# WiLoV2.net
KiCad netlist of a schematic drawn in EAGLE
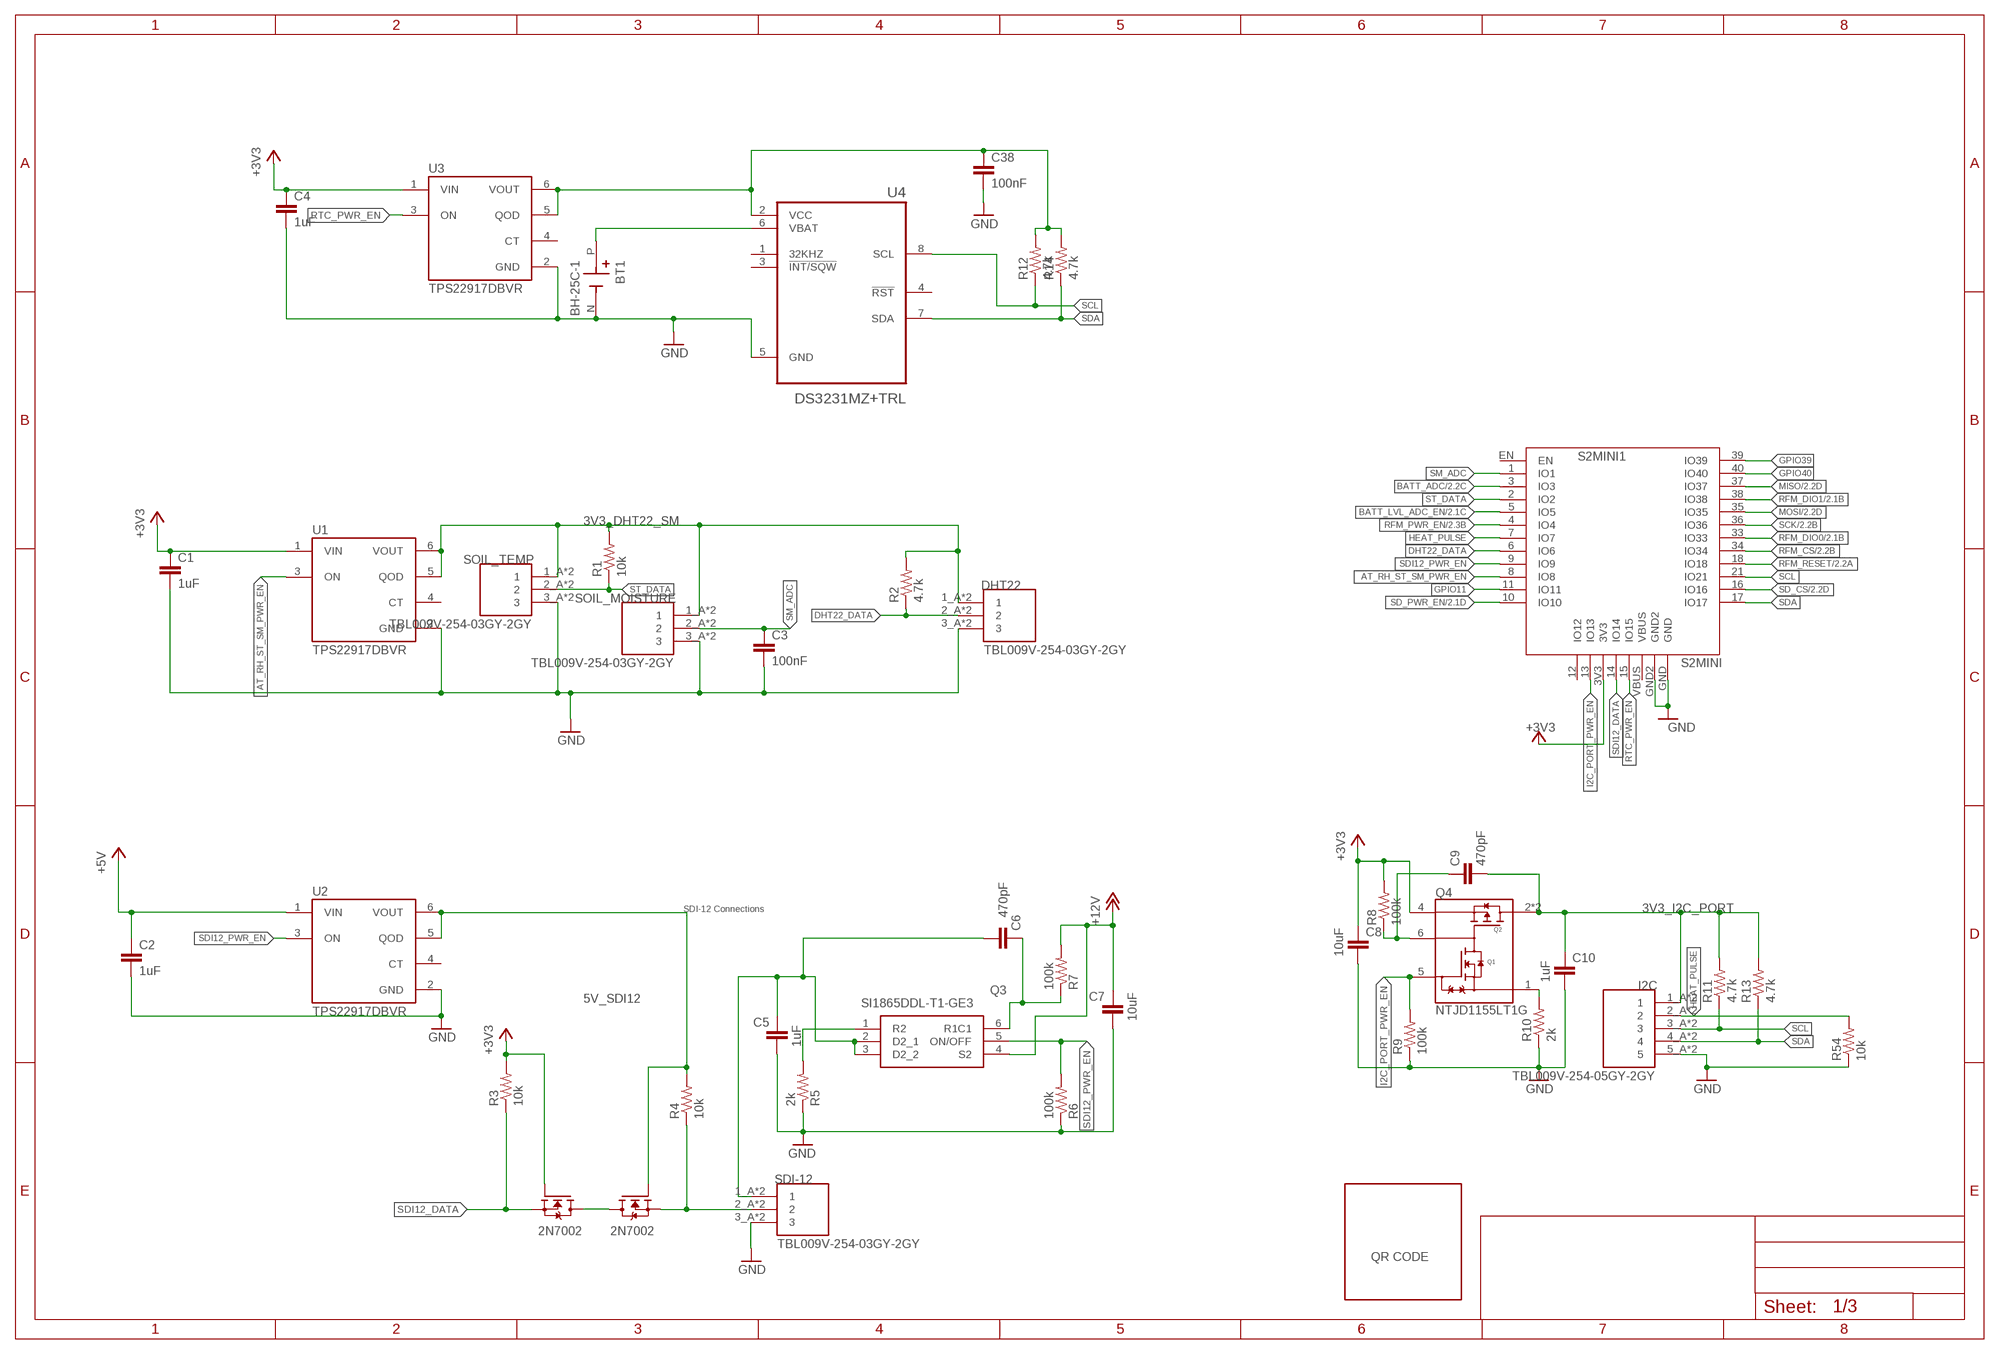
[diagram p0: schematic, sheet 1]
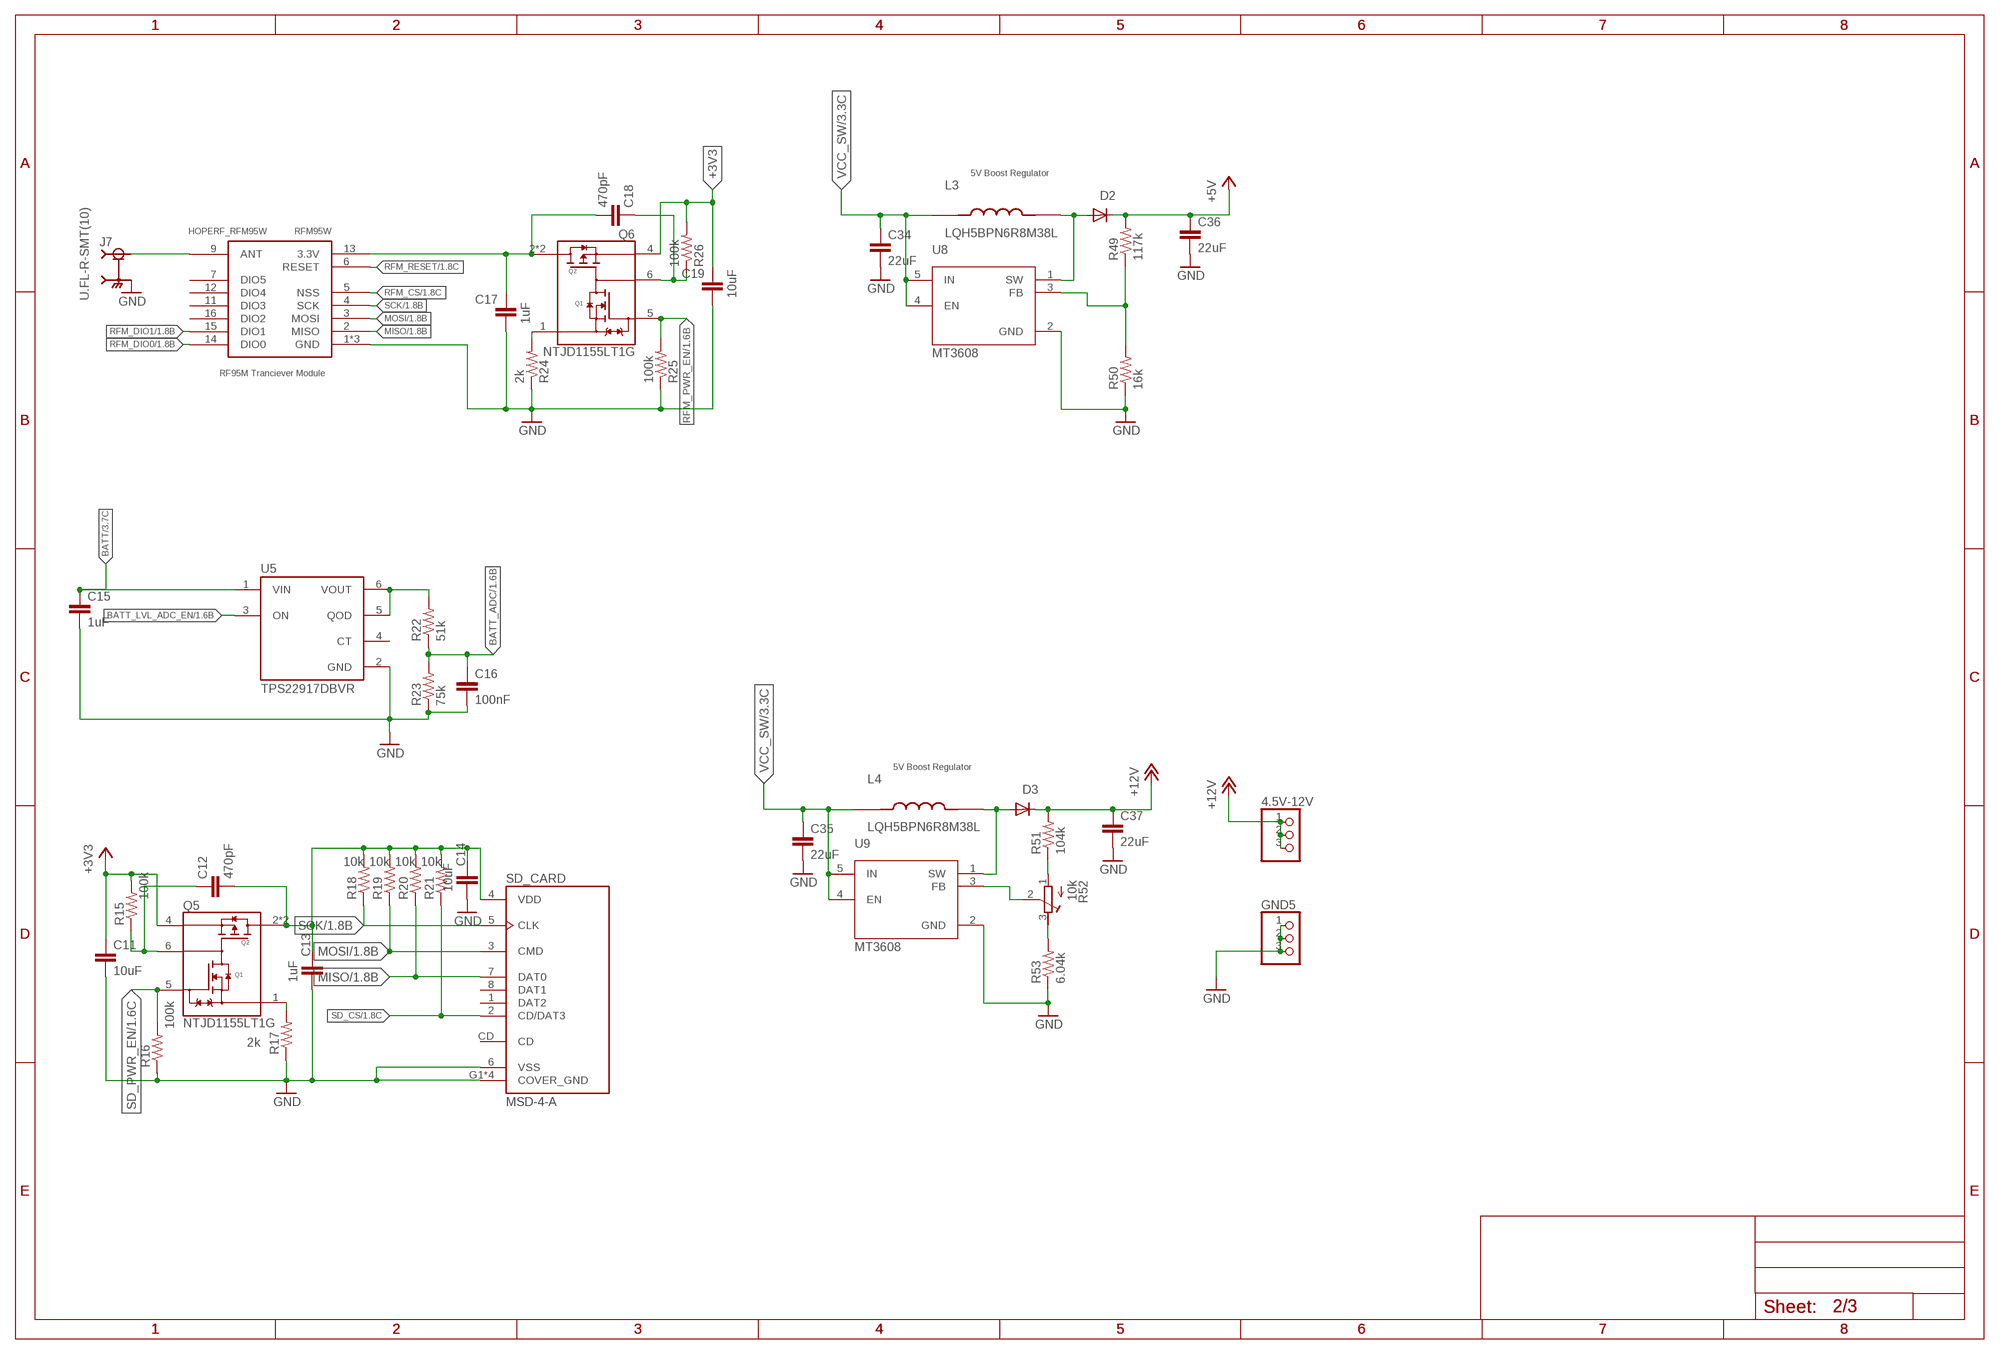
[diagram p1: schematic, sheet 2]
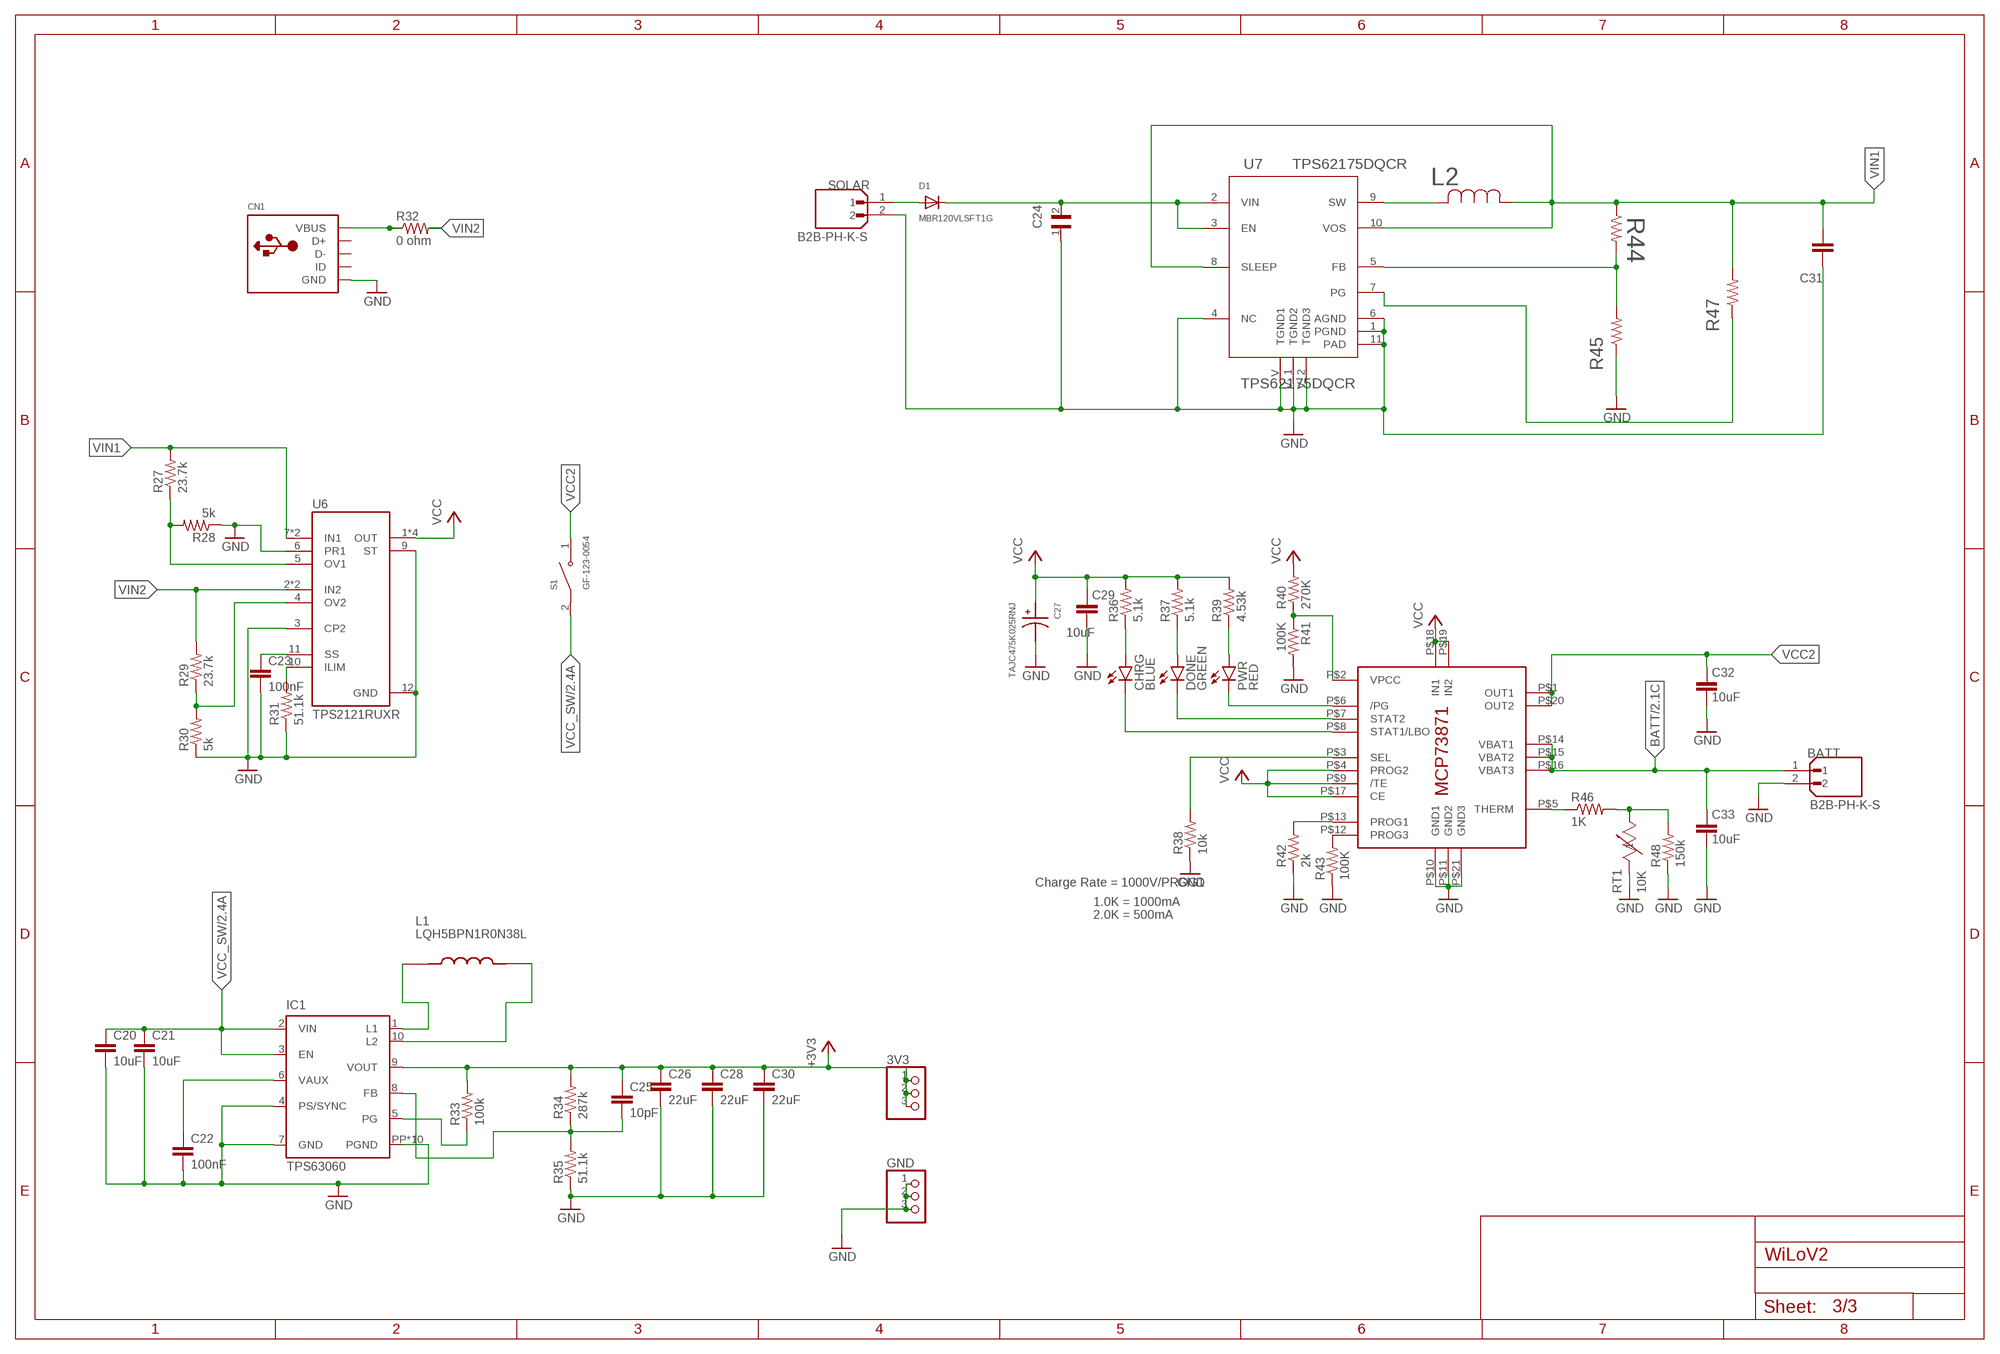
[diagram p2: schematic, sheet 3]

(export (version "E")
  (design (tool "Eeschema 10.0.6"))
  (components
    (comp (ref "3V3")
      (value "PINHD-1X3")
      (footprint "eagle-import:1X03")
      (fields (field (name "MPN") "61300311121"))
      (libsource (lib "eagle-import") (part "PINHD-1X3"))
    )
    (comp (ref "BATT")
      (value "B2B-PH-K-S")
      (footprint "eagle-import:JST_B2B-PH-K-S")
      (fields (field (name "MANUFACTURER") "JST"))
      (libsource (lib "eagle-import") (part "B2B-PH-K-S"))
    )
    (comp (ref "C20")
      (value "10uF")
      (footprint "eagle-import:C0805")
      (fields (field (name "MPN") "GRM21BR61C106KE15K"))
      (libsource (lib "eagle-import") (part "rcl@2_C-EUC0805"))
    )
    (comp (ref "C21")
      (value "10uF")
      (footprint "eagle-import:C0805")
      (fields (field (name "MPN") "GRM21BR61C106KE15K"))
      (libsource (lib "eagle-import") (part "rcl@2_C-EUC0805"))
    )
    (comp (ref "C22")
      (value "100nF")
      (footprint "eagle-import:C0805")
      (fields (field (name "MPN") "KGM21NR71E104KT"))
      (libsource (lib "eagle-import") (part "rcl@2_C-EUC0805"))
    )
    (comp (ref "C23")
      (value "100nF")
      (footprint "eagle-import:C0805")
      (fields (field (name "MPN") "KGM21NR71E104KT"))
      (libsource (lib "eagle-import") (part "rcl@2_C-EUC0805"))
    )
    (comp (ref "C24")
      (value "2.2uF")
      (footprint "eagle-import:CAPC2012X145N")
      (fields (field (name "MPN") "CGA4J3X7R1H225K125AB"))
      (libsource (lib "eagle-import") (part "CGA4J3X7R1H225K125AB"))
    )
    (comp (ref "C25")
      (value "10pF")
      (footprint "eagle-import:C0805")
      (fields (field (name "MPN") "C0805C100JDGACTU"))
      (libsource (lib "eagle-import") (part "rcl@2_C-EUC0805"))
    )
    (comp (ref "C26")
      (value "22uF")
      (footprint "eagle-import:C0805")
      (fields (field (name "MPN") "CL21A226MOQNNNE"))
      (libsource (lib "eagle-import") (part "rcl@2_C-EUC0805"))
    )
    (comp (ref "C27")
      (value "TAJC475K025RNJ")
      (footprint "eagle-import:CAPPM6032X280N")
      (fields (field (name "MANUFACTURER") "AVX"))
      (libsource (lib "eagle-import") (part "TAJC475K025RNJ"))
    )
    (comp (ref "C28")
      (value "22uF")
      (footprint "eagle-import:C0805")
      (fields (field (name "MPN") "CL21A226MOQNNNE"))
      (libsource (lib "eagle-import") (part "rcl@2_C-EUC0805"))
    )
    (comp (ref "C29")
      (value "10uF")
      (footprint "eagle-import:C0805")
      (fields (field (name "MPN") "GRM21BR61C106KE15K"))
      (libsource (lib "eagle-import") (part "rcl@2_C-EUC0805"))
    )
    (comp (ref "C30")
      (value "22uF")
      (footprint "eagle-import:C0805")
      (fields (field (name "MPN") "CL21A226MOQNNNE"))
      (libsource (lib "eagle-import") (part "rcl@2_C-EUC0805"))
    )
    (comp (ref "C31")
      (value "22uF")
      (footprint "eagle-import:C0805")
      (fields (field (name "MPN") "CL21A226MOQNNNE"))
      (libsource (lib "eagle-import") (part "rcl_334_C-EUC0805"))
    )
    (comp (ref "C32")
      (value "10uF")
      (footprint "eagle-import:C0805")
      (fields (field (name "MPN") "GRM21BR61C106KE15K"))
      (libsource (lib "eagle-import") (part "rcl@2_C-EUC0805"))
    )
    (comp (ref "C33")
      (value "10uF")
      (footprint "eagle-import:C0805")
      (fields (field (name "MPN") "GRM21BR61C106KE15K"))
      (libsource (lib "eagle-import") (part "rcl@2_C-EUC0805"))
    )
    (comp (ref "CHRG")
      (value "BLUE")
      (footprint "eagle-import:SML0603")
      (fields (field (name "MPN") "XZCFBB53W-8VF"))
      (libsource (lib "eagle-import") (part "LEDSML0603"))
    )
    (comp (ref "CN1")
      (value "USBMINIB")
      (footprint "eagle-import:USB-MINIB")
      (fields (field (name "MPN") "690-005-299-043"))
      (libsource (lib "eagle-import") (part "USBMINIB"))
    )
    (comp (ref "D1")
      (value "MBR120VLSFT1G")
      (footprint "eagle-import:SOD-123FL")
      (libsource (lib "eagle-import") (part "DIODE_SOD-123FL"))
    )
    (comp (ref "DONE")
      (value "GREEN")
      (footprint "eagle-import:SML0603")
      (fields (field (name "MPN") "XZCDGK53W-8VF"))
      (libsource (lib "eagle-import") (part "LEDSML0603"))
    )
    (comp (ref "GND")
      (value "PINHD-1X3")
      (footprint "eagle-import:1X03")
      (fields (field (name "MPN") "61300311121"))
      (libsource (lib "eagle-import") (part "PINHD-1X3"))
    )
    (comp (ref "IC1")
      (value "TPS63060")
      (footprint "eagle-import:DSC-S-PWSON-N10")
      (fields (field (name "MPN") "TPS63060DSCR"))
      (libsource (lib "eagle-import") (part "TPS63060"))
    )
    (comp (ref "IC2")
      (value "MCP73871")
      (footprint "eagle-import:QFN20_4MM")
      (fields (field (name "MPN") "MCP73871T-2CCI/ML"))
      (libsource (lib "eagle-import") (part "MCP73871"))
    )
    (comp (ref "L1")
      (value "LQH5BPN1R0N38L")
      (footprint "eagle-import:IND_LQH5BPN1R0N38L")
      (fields (field (name "MANUFACTURER") "Murata"))
      (libsource (lib "eagle-import") (part "LQH5BPN1R0N38L"))
    )
    (comp (ref "L2")
      (value "10uH")
      (footprint "eagle-import:IND_IFSC_1515AH_VIS-M")
      (fields
        (field (name "MANUFACTURER_PART_NUMBER") "IFSC1515AHER100M01")
        (field (name "COPYRIGHT") "Copyright (C) 2025 Ultra Librarian. All rights reserved.")
      )
      (libsource (lib "eagle-import") (part "IFSC1515AHER100M01IND_IFSC_1515AH_VIS-M"))
    )
    (comp (ref "PWR")
      (value "RED")
      (footprint "eagle-import:SML0603")
      (fields (field (name "MPN") "XZCM2CRK53WA-8VF"))
      (libsource (lib "eagle-import") (part "LEDSML0603"))
    )
    (comp (ref "R27")
      (value "23.7k")
      (footprint "eagle-import:R0603")
      (fields (field (name "MPN") "ERJ-3EKF2372V"))
      (libsource (lib "eagle-import") (part "rcl@2_R-US_R0603"))
    )
    (comp (ref "R28")
      (value "5k")
      (footprint "eagle-import:R0603")
      (fields (field (name "MPN") "RN73A1J5K0FTD"))
      (libsource (lib "eagle-import") (part "rcl@2_R-US_R0603"))
    )
    (comp (ref "R29")
      (value "23.7k")
      (footprint "eagle-import:R0603")
      (fields (field (name "MPN") "ERJ-3EKF2372V"))
      (libsource (lib "eagle-import") (part "rcl@2_R-US_R0603"))
    )
    (comp (ref "R30")
      (value "5k")
      (footprint "eagle-import:R0603")
      (fields (field (name "MPN") "RN73A1J5K0FTD"))
      (libsource (lib "eagle-import") (part "rcl@2_R-US_R0603"))
    )
    (comp (ref "R31")
      (value "51.1k")
      (footprint "eagle-import:R0603")
      (fields (field (name "MPN") "RC0603FR-0751K1L "))
      (libsource (lib "eagle-import") (part "R-US_R0603"))
    )
    (comp (ref "R32")
      (value "0 ohm")
      (footprint "eagle-import:R0805")
      (fields (field (name "MPN") "ERJ-6GEY0R00V"))
      (libsource (lib "eagle-import") (part "R-US_R0805"))
    )
    (comp (ref "R33")
      (value "100k")
      (footprint "eagle-import:R0603")
      (fields (field (name "MPN") "CRG0603F100K"))
      (libsource (lib "eagle-import") (part "rcl@2_R-US_R0603"))
    )
    (comp (ref "R34")
      (value "287k")
      (footprint "eagle-import:R0603")
      (fields (field (name "MPN") "ERJ-3EKF2873V"))
      (libsource (lib "eagle-import") (part "rcl_R-US_R0603"))
    )
    (comp (ref "R35")
      (value "51.1k")
      (footprint "eagle-import:R0603")
      (fields (field (name "MPN") "RC0603FR-0751K1L"))
      (libsource (lib "eagle-import") (part "rcl_R-US_R0603"))
    )
    (comp (ref "R36")
      (value "5.1k")
      (footprint "eagle-import:R0603")
      (fields (field (name "MPN") "ERA-3ARW512V"))
      (libsource (lib "eagle-import") (part "rcl@2_R-US_R0603"))
    )
    (comp (ref "R37")
      (value "5.1k")
      (footprint "eagle-import:R0603")
      (fields (field (name "MPN") "ERA-3ARW512V"))
      (libsource (lib "eagle-import") (part "rcl@2_R-US_R0603"))
    )
    (comp (ref "R38")
      (value "10k")
      (footprint "eagle-import:R0603")
      (fields (field (name "MPN") "ERJ-U03F1002V"))
      (libsource (lib "eagle-import") (part "rcl@2_R-US_R0603"))
    )
    (comp (ref "R39")
      (value "4.53k")
      (footprint "eagle-import:R0603")
      (fields (field (name "MPN") "ERJ-3EKF4531V"))
      (libsource (lib "eagle-import") (part "rcl@2_R-US_R0603"))
    )
    (comp (ref "R40")
      (value "270K")
      (footprint "eagle-import:R0603")
      (fields (field (name "MPN") "ERJ-3EKF2703V"))
      (libsource (lib "eagle-import") (part "rcl@2_R-US_R0603"))
    )
    (comp (ref "R41")
      (value "100K")
      (footprint "eagle-import:R0805")
      (fields (field (name "MPN") "RC0805FR-07100KL"))
      (libsource (lib "eagle-import") (part "R-US_R0805"))
    )
    (comp (ref "R42")
      (value "2k")
      (footprint "eagle-import:R0603")
      (fields (field (name "MPN") "RC0603FR-072KL"))
      (libsource (lib "eagle-import") (part "rcl@2_R-US_R0603"))
    )
    (comp (ref "R43")
      (value "100K")
      (footprint "eagle-import:R0805")
      (fields (field (name "MPN") "RC0805FR-07100KL"))
      (libsource (lib "eagle-import") (part "R-US_R0805"))
    )
    (comp (ref "R44")
      (value "105k")
      (footprint "eagle-import:R0603")
      (fields (field (name "MPN") "AC0603FR-07105KL"))
      (libsource (lib "eagle-import") (part "rcl@2_R-US_R0603"))
    )
    (comp (ref "R45")
      (value "20k")
      (footprint "eagle-import:R0603")
      (fields (field (name "MPN") "RC0603FR-0720KL"))
      (libsource (lib "eagle-import") (part "rcl@2_R-US_R0603"))
    )
    (comp (ref "R46")
      (value "1K")
      (footprint "eagle-import:R0603")
      (fields (field (name "MPN") "RMCF0603FT1K00"))
      (libsource (lib "eagle-import") (part "rcl@2_R-US_R0603"))
    )
    (comp (ref "R47")
      (value "100k")
      (footprint "eagle-import:R0603")
      (fields (field (name "MPN") "CRG0603F100K"))
      (libsource (lib "eagle-import") (part "rcl@2_R-US_R0603"))
    )
    (comp (ref "R48")
      (value "150k")
      (footprint "eagle-import:R0603")
      (fields (field (name "MPN") "ERJ-3EKF1503V"))
      (libsource (lib "eagle-import") (part "rcl@2_R-US_R0603"))
    )
    (comp (ref "RT1")
      (value "10K")
      (footprint "eagle-import:G1_USS")
      (fields
        (field (name "MANUFACTURER_PART_NUMBER") "103JG1F")
        (field (name "COPYRIGHT") "Copyright (C) 2025 Ultra Librarian. All rights reserved.")
      )
      (libsource (lib "eagle-import") (part "103JG1F"))
    )
    (comp (ref "S1")
      (value "GF-123-0054")
      (footprint "eagle-import:SW_GF-123-0054")
      (fields (field (name "MANUFACTURER") "CW Industries "))
      (libsource (lib "eagle-import") (part "GF-123-0054"))
    )
    (comp (ref "SOLAR")
      (value "B2B-PH-K-S")
      (footprint "eagle-import:JST_B2B-PH-K-S")
      (fields (field (name "MANUFACTURER") "JST"))
      (libsource (lib "eagle-import") (part "B2B-PH-K-S"))
    )
    (comp (ref "U6")
      (value "TPS2121RUXR")
      (footprint "eagle-import:IC_TPS2121RUXR")
      (fields (field (name "MANUFACTURER") "TEXAS INSTRUMENTS"))
      (libsource (lib "eagle-import") (part "TPS2121RUXR"))
    )
    (comp (ref "U7")
      (value "TPS62175DQCR")
      (footprint "eagle-import:DQC0010A")
      (fields (field (name "COPYRIGHT") "Copyright (C) 2025 Ultra Librarian. All rights reserved."))
      (libsource (lib "eagle-import") (part "TPS62175DQCR"))
    )
    (comp (ref "4.5V-12V")
      (value "PINHD-1X3")
      (footprint "eagle-import:1X03")
      (fields (field (name "MPN") "61300311121"))
      (libsource (lib "eagle-import") (part "PINHD-1X3"))
    )
    (comp (ref "C11")
      (value "10uF")
      (footprint "eagle-import:C0805")
      (fields (field (name "MPN") "GRM21BR61C106KE15K"))
      (libsource (lib "eagle-import") (part "rcl@2_C-EUC0805"))
    )
    (comp (ref "C12")
      (value "470pF")
      (footprint "eagle-import:C0805")
      (fields (field (name "MPN") "CC0805JRNPOBBN471"))
      (libsource (lib "eagle-import") (part "rcl@2_C-EUC0805"))
    )
    (comp (ref "C13")
      (value "1uF")
      (footprint "eagle-import:C0805")
      (fields (field (name "MPN") "CC0805KKX7R9BB105"))
      (libsource (lib "eagle-import") (part "rcl@2_C-EUC0805"))
    )
    (comp (ref "C14")
      (value "10uF")
      (footprint "eagle-import:C0805")
      (fields (field (name "MPN") "GRM21BR61C106KE15K"))
      (libsource (lib "eagle-import") (part "rcl@2_C-EUC0805"))
    )
    (comp (ref "C15")
      (value "1uF")
      (footprint "eagle-import:C0805")
      (fields (field (name "MPN") "CC0805KKX7R9BB105"))
      (libsource (lib "eagle-import") (part "rcl@2_C-EUC0805"))
    )
    (comp (ref "C16")
      (value "100nF")
      (footprint "eagle-import:C0805")
      (fields (field (name "MPN") "KGM21NR71E104KT"))
      (libsource (lib "eagle-import") (part "rcl@2_C-EUC0805"))
    )
    (comp (ref "C17")
      (value "1uF")
      (footprint "eagle-import:C0805")
      (fields (field (name "MPN") "CC0805KKX7R9BB105"))
      (libsource (lib "eagle-import") (part "rcl@2_C-EUC0805"))
    )
    (comp (ref "C18")
      (value "470pF")
      (footprint "eagle-import:C0805")
      (fields (field (name "MPN") "CC0805JRNPOBBN471"))
      (libsource (lib "eagle-import") (part "rcl@2_C-EUC0805"))
    )
    (comp (ref "C19")
      (value "10uF")
      (footprint "eagle-import:C0805")
      (fields (field (name "MPN") "GRM21BR61C106KE15K"))
      (libsource (lib "eagle-import") (part "rcl@2_C-EUC0805"))
    )
    (comp (ref "C34")
      (value "22uF")
      (footprint "eagle-import:C0805")
      (fields (field (name "MPN") "CL21A226MOQNNNE"))
      (libsource (lib "eagle-import") (part "rcl@2_C-EUC0805"))
    )
    (comp (ref "C35")
      (value "22uF")
      (footprint "eagle-import:C0805")
      (fields (field (name "MPN") "CL21A226MOQNNNE"))
      (libsource (lib "eagle-import") (part "rcl@2_C-EUC0805"))
    )
    (comp (ref "C36")
      (value "22uF")
      (footprint "eagle-import:C0805")
      (fields (field (name "MPN") "CL21A226MOQNNNE"))
      (libsource (lib "eagle-import") (part "rcl@2_C-EUC0805"))
    )
    (comp (ref "C37")
      (value "22uF")
      (footprint "eagle-import:C0805")
      (fields (field (name "MPN") "CL21A226MOQNNNE"))
      (libsource (lib "eagle-import") (part "rcl@2_C-EUC0805"))
    )
    (comp (ref "D2")
      (value "DIODE_SOD-123FL")
      (footprint "eagle-import:SOD-123FL")
      (fields (field (name "MPN") "MBR120VLSFT1G"))
      (libsource (lib "eagle-import") (part "DIODE_SOD-123FL"))
    )
    (comp (ref "D3")
      (value "DIODE_SOD-123FL")
      (footprint "eagle-import:SOD-123FL")
      (fields (field (name "MPN") "MBR120VLSFT1G"))
      (libsource (lib "eagle-import") (part "DIODE_SOD-123FL"))
    )
    (comp (ref "GND5")
      (value "PINHD-1X3")
      (footprint "eagle-import:1X03")
      (fields (field (name "MPN") "61300311121"))
      (libsource (lib "eagle-import") (part "PINHD-1X3"))
    )
    (comp (ref "J7")
      (value "U.FL-R-SMT(10)")
      (footprint "eagle-import:HRS_U.FL-R-SMT(10)")
      (fields
        (field (name "MF") "Hirose")
        (field (name "MP") "U.FL-R-SMT_10_")
        (field (name "MPN") "U.FL-R-SMT-1(01)")
      )
      (libsource (lib "eagle-import") (part "U.FL-R-SMT(10)"))
    )
    (comp (ref "L3")
      (value "LQH5BPN6R8M38L")
      (footprint "eagle-import:IND_LQH5BPN6R8M38L")
      (fields (field (name "MANUFACTURER") "Murata"))
      (libsource (lib "eagle-import") (part "LQH5BPN6R8M38L"))
    )
    (comp (ref "L4")
      (value "LQH5BPN6R8M38L")
      (footprint "eagle-import:IND_LQH5BPN6R8M38L")
      (fields (field (name "MANUFACTURER") "Murata"))
      (libsource (lib "eagle-import") (part "LQH5BPN6R8M38L"))
    )
    (comp (ref "Q5")
      (value "NTJD1155LT1G")
      (footprint "eagle-import:TRANS_NTJD1155LT1G")
      (fields (field (name "MF") "ON Semiconductor"))
      (libsource (lib "eagle-import") (part "NTJD1155LT1G"))
    )
    (comp (ref "Q6")
      (value "NTJD1155LT1G")
      (footprint "eagle-import:TRANS_NTJD1155LT1G")
      (fields (field (name "MF") "ON Semiconductor"))
      (libsource (lib "eagle-import") (part "NTJD1155LT1G"))
    )
    (comp (ref "R15")
      (value "100k")
      (footprint "eagle-import:R0603")
      (fields (field (name "MPN") "CRG0603F100K"))
      (libsource (lib "eagle-import") (part "rcl@2_R-US_R0603"))
    )
    (comp (ref "R16")
      (value "100k")
      (footprint "eagle-import:R0603")
      (fields (field (name "MPN") "CRG0603F100K"))
      (libsource (lib "eagle-import") (part "rcl@2_R-US_R0603"))
    )
    (comp (ref "R17")
      (value "2k")
      (footprint "eagle-import:R0603")
      (fields (field (name "MPN") "RC0603FR-072KL"))
      (libsource (lib "eagle-import") (part "rcl_R-US_R0603"))
    )
    (comp (ref "R18")
      (value "10k")
      (footprint "eagle-import:R0603")
      (fields (field (name "MPN") "ERJ-U03F1002V"))
      (libsource (lib "eagle-import") (part "rcl@2_R-US_R0603"))
    )
    (comp (ref "R19")
      (value "10k")
      (footprint "eagle-import:R0603")
      (fields (field (name "MPN") "ERJ-U03F1002V"))
      (libsource (lib "eagle-import") (part "rcl@2_R-US_R0603"))
    )
    (comp (ref "R20")
      (value "10k")
      (footprint "eagle-import:R0603")
      (fields (field (name "MPN") "ERJ-U03F1002V"))
      (libsource (lib "eagle-import") (part "rcl@2_R-US_R0603"))
    )
    (comp (ref "R21")
      (value "10k")
      (footprint "eagle-import:R0603")
      (fields (field (name "MPN") "ERJ-U03F1002V"))
      (libsource (lib "eagle-import") (part "rcl@2_R-US_R0603"))
    )
    (comp (ref "R22")
      (value "51k")
      (footprint "eagle-import:R0603")
      (fields (field (name "MPN") "RC0603FR-0751KL"))
      (libsource (lib "eagle-import") (part "rcl_R-US_R0603"))
    )
    (comp (ref "R23")
      (value "75k")
      (footprint "eagle-import:R0603")
      (fields (field (name "MPN") "AC0603FR-0775KL"))
      (libsource (lib "eagle-import") (part "rcl_R-US_R0603"))
    )
    (comp (ref "R24")
      (value "2k")
      (footprint "eagle-import:R0603")
      (fields (field (name "MPN") "RC0603FR-072KL"))
      (libsource (lib "eagle-import") (part "rcl_R-US_R0603"))
    )
    (comp (ref "R25")
      (value "100k")
      (footprint "eagle-import:R0603")
      (fields (field (name "MPN") "CRG0603F100K"))
      (libsource (lib "eagle-import") (part "rcl_R-US_R0603"))
    )
    (comp (ref "R26")
      (value "100k")
      (footprint "eagle-import:R0603")
      (fields (field (name "MPN") "CRG0603F100K"))
      (libsource (lib "eagle-import") (part "rcl_R-US_R0603"))
    )
    (comp (ref "R49")
      (value "117k")
      (footprint "eagle-import:R0603")
      (fields (field (name "MPN") "RT0603DRE07117KL"))
      (libsource (lib "eagle-import") (part "rcl_334_R-US_R0603"))
    )
    (comp (ref "R50")
      (value "16k")
      (footprint "eagle-import:R0603")
      (fields (field (name "MPN") "RC0603FR-0716KL"))
      (libsource (lib "eagle-import") (part "rcl_334_R-US_R0603"))
    )
    (comp (ref "R51")
      (value "104k")
      (footprint "eagle-import:R0603")
      (fields (field (name "MPN") "RN73H1JTTD1043B50"))
      (libsource (lib "eagle-import") (part "rcl_334_R-US_R0603"))
    )
    (comp (ref "R52")
      (value "10k")
      (footprint "eagle-import:RTRIM3296W")
      (fields (field (name "MPN") "3296W-1-103RLF"))
      (libsource (lib "eagle-import") (part "R-TRIMM3296W"))
    )
    (comp (ref "R53")
      (value "6.04k")
      (footprint "eagle-import:R0603")
      (fields (field (name "MPN") "ERJ-3EKF6041V"))
      (libsource (lib "eagle-import") (part "rcl_334_R-US_R0603"))
    )
    (comp (ref "RFM95W")
      (value "HOPERF_RFM95W")
      (footprint "eagle-import:HOPERF_RFM95W")
      (fields (field (name "MPN") "RFM95W-868S2"))
      (libsource (lib "eagle-import") (part "HOPERF_RFM95W"))
    )
    (comp (ref "SD_CARD")
      (value "MSD-4-A")
      (footprint "eagle-import:CUI_MSD-4-A")
      (fields (field (name "MANUFACTURER") "CUI Devices"))
      (libsource (lib "eagle-import") (part "MSD-4-A"))
    )
    (comp (ref "U5")
      (value "TPS22917DBVR")
      (footprint "eagle-import:SOT95P280X145-6N")
      (fields (field (name "MANUFACTURER") "Texas Instruments") (field (name "MPN") "TPS22917DBVT"))
      (libsource (lib "eagle-import") (part "TPS22917DBVR"))
    )
    (comp (ref "U8")
      (value "MT3608")
      (footprint "eagle-import:SOT95P280X145-6N")
      (fields (field (name "MF") "Aerosemi Technology Co., Ltd"))
      (libsource (lib "eagle-import") (part "MT3608"))
    )
    (comp (ref "U9")
      (value "MT3608")
      (footprint "eagle-import:SOT95P280X145-6N")
      (fields (field (name "MF") "Aerosemi Technology Co., Ltd"))
      (libsource (lib "eagle-import") (part "MT3608"))
    )
    (comp (ref "BT1")
      (value "BH-25C-1")
      (footprint "eagle-import:BAT_BH-25C-1")
      (fields (field (name "MANUFACTURER") "Adam Tech"))
      (libsource (lib "eagle-import") (part "BH-25C-1"))
    )
    (comp (ref "C1")
      (value "1uF")
      (footprint "eagle-import:C0805")
      (fields (field (name "MPN") "CC0805KKX7R9BB105"))
      (libsource (lib "eagle-import") (part "rcl@2_C-EUC0805"))
    )
    (comp (ref "C2")
      (value "1uF")
      (footprint "eagle-import:C0805")
      (fields (field (name "MPN") "CC0805KKX7R9BB105"))
      (libsource (lib "eagle-import") (part "rcl_334_C-EUC0805"))
    )
    (comp (ref "C3")
      (value "100nF")
      (footprint "eagle-import:C0805")
      (fields (field (name "MPN") "KGM21NR71E104KT"))
      (libsource (lib "eagle-import") (part "C-EUC0805"))
    )
    (comp (ref "C4")
      (value "1uF")
      (footprint "eagle-import:C0805")
      (fields (field (name "MPN") "CC0805KKX7R9BB105"))
      (libsource (lib "eagle-import") (part "rcl@2_C-EUC0805"))
    )
    (comp (ref "C5")
      (value "1uF")
      (footprint "eagle-import:C0805")
      (fields (field (name "MPN") "CC0805KKX7R9BB105"))
      (libsource (lib "eagle-import") (part "C-EUC0805"))
    )
    (comp (ref "C6")
      (value "470pF")
      (footprint "eagle-import:C0805")
      (fields (field (name "MPN") "CC0805JRNPOBBN471"))
      (libsource (lib "eagle-import") (part "C-EUC0805"))
    )
    (comp (ref "C7")
      (value "10uF")
      (footprint "eagle-import:C0805")
      (fields (field (name "MPN") "GRM21BR61C106KE15K"))
      (libsource (lib "eagle-import") (part "C-EUC0805"))
    )
    (comp (ref "C8")
      (value "10uF")
      (footprint "eagle-import:C0805")
      (fields (field (name "MPN") "GRM21BR61C106KE15K"))
      (libsource (lib "eagle-import") (part "C-EUC0805"))
    )
    (comp (ref "C9")
      (value "470pF")
      (footprint "eagle-import:C0805")
      (fields (field (name "MPN") "CC0805JRNPOBBN471"))
      (libsource (lib "eagle-import") (part "C-EUC0805"))
    )
    (comp (ref "C10")
      (value "1uF")
      (footprint "eagle-import:C0805")
      (fields (field (name "MPN") "CC0805KKX7R9BB105"))
      (libsource (lib "eagle-import") (part "C-EUC0805"))
    )
    (comp (ref "C38")
      (value "100nF")
      (footprint "eagle-import:C0805")
      (fields (field (name "MPN") "KGM21NR71E104KT"))
      (libsource (lib "eagle-import") (part "rcl_334_C-EUC0805"))
    )
    (comp (ref "DHT22")
      (value "TBL009V-254-03GY-2GY")
      (footprint "eagle-import:CUI_TBL009V-254-03GY-2GY")
      (fields (field (name "MANUFACTURER") "CUI"))
      (libsource (lib "eagle-import") (part "TBL009V-254-03GY-2GY"))
    )
    (comp (ref "I2C")
      (value "TBL009V-254-05GY-2GY")
      (footprint "eagle-import:CUI_TBL009V-254-05GY-2GY")
      (fields (field (name "MANUFACTURER") "CUI"))
      (libsource (lib "eagle-import") (part "TBL009V-254-05GY-2GY"))
    )
    (comp (ref "Q1")
      (value "2N7002")
      (footprint "eagle-import:SOT95P240X111-3N")
      (fields (field (name "MF") "ON Semiconductor"))
      (libsource (lib "eagle-import") (part "2N7002"))
    )
    (comp (ref "Q2")
      (value "2N7002")
      (footprint "eagle-import:SOT95P240X111-3N")
      (fields (field (name "MF") "ON Semiconductor"))
      (libsource (lib "eagle-import") (part "2N7002"))
    )
    (comp (ref "Q3")
      (value "SI1865DDL-T1-GE3")
      (footprint "eagle-import:SOT65P210X110-6N")
      (fields (field (name "MOUSER_PART_NUMBER") "78-SI1865DDL-T1-GE3"))
      (libsource (lib "eagle-import") (part "SI1865DDL-T1-GE3"))
    )
    (comp (ref "Q4")
      (value "NTJD1155LT1G")
      (footprint "eagle-import:TRANS_NTJD1155LT1G")
      (fields (field (name "MF") "ON Semiconductor"))
      (libsource (lib "eagle-import") (part "NTJD1155LT1G"))
    )
    (comp (ref "QR_CODE")
      (value "QR_CODE")
      (footprint "eagle-import:QR_CODE")
      (libsource (lib "eagle-import") (part "QR_CODE"))
    )
    (comp (ref "R1")
      (value "10k")
      (footprint "eagle-import:R0603")
      (fields (field (name "MPN") "ERJ-U03F1002V"))
      (libsource (lib "eagle-import") (part "rcl_R-US_R0603"))
    )
    (comp (ref "R2")
      (value "4.7k")
      (footprint "eagle-import:R0603")
      (fields (field (name "MPN") "RK73G1JTTD4701C"))
      (libsource (lib "eagle-import") (part "rcl_R-US_R0603"))
    )
    (comp (ref "R3")
      (value "10k")
      (footprint "eagle-import:R0603")
      (fields (field (name "MPN") "ERJ-U03F1002V"))
      (libsource (lib "eagle-import") (part "rcl_R-US_R0603"))
    )
    (comp (ref "R4")
      (value "10k")
      (footprint "eagle-import:R0603")
      (fields (field (name "MPN") "ERJ-U03F1002V"))
      (libsource (lib "eagle-import") (part "rcl_R-US_R0603"))
    )
    (comp (ref "R5")
      (value "2k")
      (footprint "eagle-import:R0603")
      (fields (field (name "MPN") "RC0603FR-072KL"))
      (libsource (lib "eagle-import") (part "rcl_R-US_R0603"))
    )
    (comp (ref "R6")
      (value "100k")
      (footprint "eagle-import:R0603")
      (fields (field (name "MPN") "CRG0603F100K"))
      (libsource (lib "eagle-import") (part "rcl_R-US_R0603"))
    )
    (comp (ref "R7")
      (value "100k")
      (footprint "eagle-import:R0603")
      (fields (field (name "MPN") "CRG0603F100K"))
      (libsource (lib "eagle-import") (part "rcl_R-US_R0603"))
    )
    (comp (ref "R8")
      (value "100k")
      (footprint "eagle-import:R0603")
      (fields (field (name "MPN") "CRG0603F100K"))
      (libsource (lib "eagle-import") (part "rcl_R-US_R0603"))
    )
    (comp (ref "R9")
      (value "100k")
      (footprint "eagle-import:R0603")
      (fields (field (name "MPN") "CRG0603F100K"))
      (libsource (lib "eagle-import") (part "rcl_R-US_R0603"))
    )
    (comp (ref "R10")
      (value "2k")
      (footprint "eagle-import:R0603")
      (fields (field (name "MPN") "RC0603FR-072KL"))
      (libsource (lib "eagle-import") (part "rcl_R-US_R0603"))
    )
    (comp (ref "R11")
      (value "4.7k")
      (footprint "eagle-import:R0603")
      (fields (field (name "MPN") "RK73G1JTTD4701C"))
      (libsource (lib "eagle-import") (part "rcl_R-US_R0603"))
    )
    (comp (ref "R12")
      (value "4.7k")
      (footprint "eagle-import:R0603")
      (fields (field (name "MPN") "RK73G1JTTD4701C"))
      (libsource (lib "eagle-import") (part "rcl_R-US_R0603"))
    )
    (comp (ref "R13")
      (value "4.7k")
      (footprint "eagle-import:R0603")
      (fields (field (name "MPN") "RK73G1JTTD4701C"))
      (libsource (lib "eagle-import") (part "rcl_R-US_R0603"))
    )
    (comp (ref "R14")
      (value "4.7k")
      (footprint "eagle-import:R0603")
      (fields (field (name "MPN") "RK73G1JTTD4701C"))
      (libsource (lib "eagle-import") (part "rcl_R-US_R0603"))
    )
    (comp (ref "R54")
      (value "10k")
      (footprint "eagle-import:R0603")
      (fields (field (name "MPN") "ERJ-U03F1002V"))
      (libsource (lib "eagle-import") (part "rcl_334_R-US_R0603"))
    )
    (comp (ref "S2MINI1")
      (value "S2MINI")
      (footprint "eagle-import:S2MINI")
      (libsource (lib "eagle-import") (part "S2MINI"))
    )
    (comp (ref "SDI-12")
      (value "TBL009V-254-03GY-2GY")
      (footprint "eagle-import:CUI_TBL009V-254-03GY-2GY")
      (fields (field (name "MANUFACTURER") "CUI"))
      (libsource (lib "eagle-import") (part "TBL009V-254-03GY-2GY"))
    )
    (comp (ref "SOIL_MOISTURE")
      (value "TBL009V-254-03GY-2GY")
      (footprint "eagle-import:CUI_TBL009V-254-03GY-2GY")
      (fields (field (name "MANUFACTURER") "CUI"))
      (libsource (lib "eagle-import") (part "TBL009V-254-03GY-2GY"))
    )
    (comp (ref "SOIL_TEMP")
      (value "TBL009V-254-03GY-2GY")
      (footprint "eagle-import:CUI_TBL009V-254-03GY-2GY")
      (fields (field (name "MANUFACTURER") "CUI"))
      (libsource (lib "eagle-import") (part "TBL009V-254-03GY-2GY"))
    )
    (comp (ref "U1")
      (value "TPS22917DBVR")
      (footprint "eagle-import:SOT95P280X145-6N")
      (fields (field (name "MANUFACTURER") "Texas Instruments") (field (name "MPN") "TPS22917DBVT"))
      (libsource (lib "eagle-import") (part "TPS22917DBVR"))
    )
    (comp (ref "U2")
      (value "TPS22917DBVR")
      (footprint "eagle-import:SOT95P280X145-6N")
      (fields (field (name "MANUFACTURER") "Texas Instruments") (field (name "MPN") "TPS22917DBVT"))
      (libsource (lib "eagle-import") (part "TPS22917DBVR"))
    )
    (comp (ref "U3")
      (value "TPS22917DBVR")
      (footprint "eagle-import:SOT95P280X145-6N")
      (fields (field (name "MANUFACTURER") "Texas Instruments") (field (name "MPN") "TPS22917DBVT"))
      (libsource (lib "eagle-import") (part "TPS22917DBVR"))
    )
    (comp (ref "U4")
      (value "DS3231MZ+TRL")
      (footprint "eagle-import:SOIC127P600X175-8N")
      (libsource (lib "eagle-import") (part "DS3231MZ+TRL"))
    )
  )
  (nets
    (net (code "1") (name "+3V3") (class "Default")
      (node (ref "3V3") (pin "1") (pinfunction "1_1") (pintype "passive"))
      (node (ref "3V3") (pin "2") (pinfunction "2_2") (pintype "passive"))
      (node (ref "3V3") (pin "3") (pinfunction "3_3") (pintype "passive"))
      (node (ref "C1") (pin "1") (pinfunction "1_1") (pintype "passive"))
      (node (ref "C11") (pin "1") (pinfunction "1_1") (pintype "passive"))
      (node (ref "C19") (pin "1") (pinfunction "1_1") (pintype "passive"))
      (node (ref "C25") (pin "1") (pinfunction "1_1") (pintype "passive"))
      (node (ref "C26") (pin "1") (pinfunction "1_1") (pintype "passive"))
      (node (ref "C28") (pin "1") (pinfunction "1_1") (pintype "passive"))
      (node (ref "C30") (pin "1") (pinfunction "1_1") (pintype "passive"))
      (node (ref "C4") (pin "1") (pinfunction "1_1") (pintype "passive"))
      (node (ref "C8") (pin "1") (pinfunction "1_1") (pintype "passive"))
      (node (ref "IC1") (pin "9") (pinfunction "VOUT_9") (pintype "output"))
      (node (ref "Q1") (pin "1") (pinfunction "G_1") (pintype "passive"))
      (node (ref "Q4") (pin "4") (pinfunction "S2_4") (pintype "passive"))
      (node (ref "Q5") (pin "4") (pinfunction "S2_4") (pintype "passive"))
      (node (ref "Q6") (pin "4") (pinfunction "S2_4") (pintype "passive"))
      (node (ref "R15") (pin "2") (pinfunction "2_2") (pintype "passive"))
      (node (ref "R26") (pin "2") (pinfunction "2_2") (pintype "passive"))
      (node (ref "R3") (pin "2") (pinfunction "2_2") (pintype "passive"))
      (node (ref "R33") (pin "2") (pinfunction "2_2") (pintype "passive"))
      (node (ref "R34") (pin "2") (pinfunction "2_2") (pintype "passive"))
      (node (ref "R8") (pin "2") (pinfunction "2_2") (pintype "passive"))
      (node (ref "S2MINI1") (pin "3V3") (pinfunction "3V3_3V3") (pintype "bidirectional"))
      (node (ref "U1") (pin "1") (pinfunction "VIN_1") (pintype "input"))
      (node (ref "U3") (pin "1") (pinfunction "VIN_1") (pintype "input"))
    )
    (net (code "2") (name "+5V") (class "Default")
      (node (ref "C2") (pin "1") (pinfunction "1_1") (pintype "passive"))
      (node (ref "C36") (pin "1") (pinfunction "1_1") (pintype "passive"))
      (node (ref "D2") (pin "C") (pinfunction "C_C") (pintype "passive"))
      (node (ref "R49") (pin "2") (pinfunction "2_2") (pintype "passive"))
      (node (ref "U2") (pin "1") (pinfunction "VIN_1") (pintype "input"))
    )
    (net (code "3") (name "+12V") (class "Default")
      (node (ref "4.5V-12V") (pin "1") (pinfunction "1_1") (pintype "passive"))
      (node (ref "4.5V-12V") (pin "2") (pinfunction "2_2") (pintype "passive"))
      (node (ref "4.5V-12V") (pin "3") (pinfunction "3_3") (pintype "passive"))
      (node (ref "C37") (pin "1") (pinfunction "1_1") (pintype "passive"))
      (node (ref "C7") (pin "1") (pinfunction "1_1") (pintype "passive"))
      (node (ref "D3") (pin "C") (pinfunction "C_C") (pintype "passive"))
      (node (ref "Q3") (pin "4") (pinfunction "S2_4") (pintype "input"))
      (node (ref "R51") (pin "2") (pinfunction "2_2") (pintype "passive"))
      (node (ref "R7") (pin "2") (pinfunction "2_2") (pintype "passive"))
    )
    (net (code "4") (name "3V3_DHT22_SM") (class "Default")
      (node (ref "DHT22") (pin "1_A") (pinfunction "1_1_A") (pintype "passive"))
      (node (ref "DHT22") (pin "1_B") (pinfunction "1_1_B") (pintype "passive"))
      (node (ref "R1") (pin "2") (pinfunction "2_2") (pintype "passive"))
      (node (ref "R2") (pin "2") (pinfunction "2_2") (pintype "passive"))
      (node (ref "SOIL_MOISTURE") (pin "1_A") (pinfunction "1_1_A") (pintype "passive"))
      (node (ref "SOIL_MOISTURE") (pin "1_B") (pinfunction "1_1_B") (pintype "passive"))
      (node (ref "SOIL_TEMP") (pin "1_A") (pinfunction "1_1_A") (pintype "passive"))
      (node (ref "SOIL_TEMP") (pin "1_B") (pinfunction "1_1_B") (pintype "passive"))
      (node (ref "U1") (pin "5") (pinfunction "QOD_5") (pintype "output"))
      (node (ref "U1") (pin "6") (pinfunction "VOUT_6") (pintype "output"))
    )
    (net (code "5") (name "3V3_I2C_PORT") (class "Default")
      (node (ref "C10") (pin "1") (pinfunction "1_1") (pintype "passive"))
      (node (ref "C9") (pin "2") (pinfunction "2_2") (pintype "passive"))
      (node (ref "I2C") (pin "1_A") (pinfunction "1_1_A") (pintype "passive"))
      (node (ref "I2C") (pin "1_B") (pinfunction "1_1_B") (pintype "passive"))
      (node (ref "Q4") (pin "2") (pinfunction "D2_2") (pintype "passive"))
      (node (ref "Q4") (pin "3") (pinfunction "D2_3") (pintype "passive"))
      (node (ref "R11") (pin "2") (pinfunction "2_2") (pintype "passive"))
      (node (ref "R13") (pin "2") (pinfunction "2_2") (pintype "passive"))
    )
    (net (code "6") (name "5V_SDI12") (class "Default")
      (node (ref "Q2") (pin "1") (pinfunction "G_1") (pintype "passive"))
      (node (ref "R4") (pin "2") (pinfunction "2_2") (pintype "passive"))
      (node (ref "U2") (pin "5") (pinfunction "QOD_5") (pintype "output"))
      (node (ref "U2") (pin "6") (pinfunction "VOUT_6") (pintype "output"))
    )
    (net (code "7") (name "AT_RH_ST_SM_PWR_EN") (class "Default")
      (node (ref "S2MINI1") (pin "8") (pinfunction "IO8_8") (pintype "bidirectional"))
      (node (ref "U1") (pin "3") (pinfunction "ON_3") (pintype "input"))
    )
    (net (code "8") (name "BATT") (class "Default")
      (node (ref "BATT") (pin "1") (pinfunction "1_1") (pintype "passive"))
      (node (ref "C15") (pin "1") (pinfunction "1_1") (pintype "passive"))
      (node (ref "C33") (pin "1") (pinfunction "1_1") (pintype "passive"))
      (node (ref "IC2") (pin "P$14") (pinfunction "VBAT1_P$14") (pintype "output"))
      (node (ref "IC2") (pin "P$15") (pinfunction "VBAT2_P$15") (pintype "output"))
      (node (ref "IC2") (pin "P$16") (pinfunction "VBAT3_P$16") (pintype "output"))
      (node (ref "U5") (pin "1") (pinfunction "VIN_1") (pintype "input"))
    )
    (net (code "9") (name "BATT_ADC") (class "Default")
      (node (ref "C16") (pin "1") (pinfunction "1_1") (pintype "passive"))
      (node (ref "R22") (pin "1") (pinfunction "1_1") (pintype "passive"))
      (node (ref "R23") (pin "2") (pinfunction "2_2") (pintype "passive"))
      (node (ref "S2MINI1") (pin "3") (pinfunction "IO3_3") (pintype "bidirectional"))
    )
    (net (code "10") (name "BATT_LVL_ADC_EN") (class "Default")
      (node (ref "S2MINI1") (pin "5") (pinfunction "IO5_5") (pintype "bidirectional"))
      (node (ref "U5") (pin "3") (pinfunction "ON_3") (pintype "input"))
    )
    (net (code "11") (name "DHT22_DATA") (class "Default")
      (node (ref "DHT22") (pin "2_A") (pinfunction "2_2_A") (pintype "passive"))
      (node (ref "DHT22") (pin "2_B") (pinfunction "2_2_B") (pintype "passive"))
      (node (ref "R2") (pin "1") (pinfunction "1_1") (pintype "passive"))
      (node (ref "S2MINI1") (pin "6") (pinfunction "IO6_6") (pintype "bidirectional"))
    )
    (net (code "12") (name "GND") (class "Default")
      (node (ref "BATT") (pin "2") (pinfunction "2_2") (pintype "passive"))
      (node (ref "BT1") (pin "N") (pinfunction "N_N") (pintype "passive"))
      (node (ref "C1") (pin "2") (pinfunction "2_2") (pintype "passive"))
      (node (ref "C10") (pin "2") (pinfunction "2_2") (pintype "passive"))
      (node (ref "C11") (pin "2") (pinfunction "2_2") (pintype "passive"))
      (node (ref "C13") (pin "2") (pinfunction "2_2") (pintype "passive"))
      (node (ref "C14") (pin "2") (pinfunction "2_2") (pintype "passive"))
      (node (ref "C15") (pin "2") (pinfunction "2_2") (pintype "passive"))
      (node (ref "C16") (pin "2") (pinfunction "2_2") (pintype "passive"))
      (node (ref "C17") (pin "2") (pinfunction "2_2") (pintype "passive"))
      (node (ref "C19") (pin "2") (pinfunction "2_2") (pintype "passive"))
      (node (ref "C2") (pin "2") (pinfunction "2_2") (pintype "passive"))
      (node (ref "C20") (pin "2") (pinfunction "2_2") (pintype "passive"))
      (node (ref "C21") (pin "2") (pinfunction "2_2") (pintype "passive"))
      (node (ref "C22") (pin "2") (pinfunction "2_2") (pintype "passive"))
      (node (ref "C23") (pin "2") (pinfunction "2_2") (pintype "passive"))
      (node (ref "C24") (pin "1") (pinfunction "1_1") (pintype "passive"))
      (node (ref "C26") (pin "2") (pinfunction "2_2") (pintype "passive"))
      (node (ref "C27") (pin "2") (pinfunction "2_2") (pintype "passive"))
      (node (ref "C28") (pin "2") (pinfunction "2_2") (pintype "passive"))
      (node (ref "C29") (pin "2") (pinfunction "2_2") (pintype "passive"))
      (node (ref "C3") (pin "2") (pinfunction "2_2") (pintype "passive"))
      (node (ref "C30") (pin "2") (pinfunction "2_2") (pintype "passive"))
      (node (ref "C31") (pin "1") (pinfunction "1_1") (pintype "passive"))
      (node (ref "C32") (pin "2") (pinfunction "2_2") (pintype "passive"))
      (node (ref "C33") (pin "2") (pinfunction "2_2") (pintype "passive"))
      (node (ref "C34") (pin "2") (pinfunction "2_2") (pintype "passive"))
      (node (ref "C35") (pin "2") (pinfunction "2_2") (pintype "passive"))
      (node (ref "C36") (pin "2") (pinfunction "2_2") (pintype "passive"))
      (node (ref "C37") (pin "2") (pinfunction "2_2") (pintype "passive"))
      (node (ref "C38") (pin "2") (pinfunction "2_2") (pintype "passive"))
      (node (ref "C4") (pin "2") (pinfunction "2_2") (pintype "passive"))
      (node (ref "C5") (pin "2") (pinfunction "2_2") (pintype "passive"))
      (node (ref "C7") (pin "2") (pinfunction "2_2") (pintype "passive"))
      (node (ref "C8") (pin "2") (pinfunction "2_2") (pintype "passive"))
      (node (ref "CN1") (pin "GND") (pinfunction "GND_GND") (pintype "power_in"))
      (node (ref "DHT22") (pin "3_A") (pinfunction "3_3_A") (pintype "passive"))
      (node (ref "DHT22") (pin "3_B") (pinfunction "3_3_B") (pintype "passive"))
      (node (ref "GND") (pin "1") (pinfunction "1_1") (pintype "passive"))
      (node (ref "GND") (pin "2") (pinfunction "2_2") (pintype "passive"))
      (node (ref "GND") (pin "3") (pinfunction "3_3") (pintype "passive"))
      (node (ref "GND5") (pin "1") (pinfunction "1_1") (pintype "passive"))
      (node (ref "GND5") (pin "2") (pinfunction "2_2") (pintype "passive"))
      (node (ref "GND5") (pin "3") (pinfunction "3_3") (pintype "passive"))
      (node (ref "I2C") (pin "5_A") (pinfunction "5_5_A") (pintype "passive"))
      (node (ref "I2C") (pin "5_B") (pinfunction "5_5_B") (pintype "passive"))
      (node (ref "IC1") (pin "4") (pinfunction "PS/SYNC_4") (pintype "input"))
      (node (ref "IC1") (pin "7") (pinfunction "GND_7") (pintype "input"))
      (node (ref "IC1") (pin "PP") (pinfunction "PGND_PP") (pintype "power_in"))
      (node (ref "IC1") (pin "PP@1") (pinfunction "PGND_PP@1") (pintype "power_in"))
      (node (ref "IC1") (pin "PP@10") (pinfunction "PGND_PP@10") (pintype "power_in"))
      (node (ref "IC1") (pin "PP@2") (pinfunction "PGND_PP@2") (pintype "power_in"))
      (node (ref "IC1") (pin "PP@3") (pinfunction "PGND_PP@3") (pintype "power_in"))
      (node (ref "IC1") (pin "PP@4") (pinfunction "PGND_PP@4") (pintype "power_in"))
      (node (ref "IC1") (pin "PP@5") (pinfunction "PGND_PP@5") (pintype "power_in"))
      (node (ref "IC1") (pin "PP@7") (pinfunction "PGND_PP@7") (pintype "power_in"))
      (node (ref "IC1") (pin "PP@8") (pinfunction "PGND_PP@8") (pintype "power_in"))
      (node (ref "IC1") (pin "PP@9") (pinfunction "PGND_PP@9") (pintype "power_in"))
      (node (ref "IC2") (pin "P$10") (pinfunction "GND1_P$10") (pintype "power_in"))
      (node (ref "IC2") (pin "P$11") (pinfunction "GND2_P$11") (pintype "power_in"))
      (node (ref "IC2") (pin "P$21") (pinfunction "GND3_P$21") (pintype "power_in"))
      (node (ref "J7") (pin "2") (pinfunction "GND_2") (pintype "passive"))
      (node (ref "J7") (pin "3") (pinfunction "GND_3") (pintype "passive"))
      (node (ref "R10") (pin "1") (pinfunction "1_1") (pintype "passive"))
      (node (ref "R16") (pin "1") (pinfunction "1_1") (pintype "passive"))
      (node (ref "R17") (pin "1") (pinfunction "1_1") (pintype "passive"))
      (node (ref "R23") (pin "1") (pinfunction "1_1") (pintype "passive"))
      (node (ref "R24") (pin "1") (pinfunction "1_1") (pintype "passive"))
      (node (ref "R25") (pin "1") (pinfunction "1_1") (pintype "passive"))
      (node (ref "R28") (pin "1") (pinfunction "1_1") (pintype "passive"))
      (node (ref "R30") (pin "1") (pinfunction "1_1") (pintype "passive"))
      (node (ref "R31") (pin "1") (pinfunction "1_1") (pintype "passive"))
      (node (ref "R35") (pin "1") (pinfunction "1_1") (pintype "passive"))
      (node (ref "R38") (pin "1") (pinfunction "1_1") (pintype "passive"))
      (node (ref "R41") (pin "2") (pinfunction "2_2") (pintype "passive"))
      (node (ref "R42") (pin "1") (pinfunction "1_1") (pintype "passive"))
      (node (ref "R43") (pin "1") (pinfunction "1_1") (pintype "passive"))
      (node (ref "R45") (pin "1") (pinfunction "1_1") (pintype "passive"))
      (node (ref "R48") (pin "1") (pinfunction "1_1") (pintype "passive"))
      (node (ref "R5") (pin "1") (pinfunction "1_1") (pintype "passive"))
      (node (ref "R50") (pin "1") (pinfunction "1_1") (pintype "passive"))
      (node (ref "R53") (pin "1") (pinfunction "1_1") (pintype "passive"))
      (node (ref "R54") (pin "1") (pinfunction "1_1") (pintype "passive"))
      (node (ref "R6") (pin "1") (pinfunction "1_1") (pintype "passive"))
      (node (ref "R9") (pin "1") (pinfunction "1_1") (pintype "passive"))
      (node (ref "RFM95W") (pin "1") (pinfunction "GND_1") (pintype "power_in"))
      (node (ref "RFM95W") (pin "10") (pinfunction "GND_10") (pintype "power_in"))
      (node (ref "RFM95W") (pin "8") (pinfunction "GND_8") (pintype "power_in"))
      (node (ref "RT1") (pin "1") (pinfunction "1_1") (pintype "passive"))
      (node (ref "S2MINI1") (pin "GND") (pinfunction "GND_GND") (pintype "bidirectional"))
      (node (ref "S2MINI1") (pin "GND2") (pinfunction "GND2_GND2") (pintype "bidirectional"))
      (node (ref "SDI-12") (pin "3_A") (pinfunction "3_3_A") (pintype "passive"))
      (node (ref "SDI-12") (pin "3_B") (pinfunction "3_3_B") (pintype "passive"))
      (node (ref "SD_CARD") (pin "6") (pinfunction "VSS_6") (pintype "power_in"))
      (node (ref "SD_CARD") (pin "G1") (pinfunction "COVER_GND_G1") (pintype "power_in"))
      (node (ref "SD_CARD") (pin "G2") (pinfunction "COVER_GND_G2") (pintype "power_in"))
      (node (ref "SD_CARD") (pin "G3") (pinfunction "COVER_GND_G3") (pintype "power_in"))
      (node (ref "SD_CARD") (pin "G4") (pinfunction "COVER_GND_G4") (pintype "power_in"))
      (node (ref "SOIL_MOISTURE") (pin "3_A") (pinfunction "3_3_A") (pintype "passive"))
      (node (ref "SOIL_MOISTURE") (pin "3_B") (pinfunction "3_3_B") (pintype "passive"))
      (node (ref "SOIL_TEMP") (pin "3_A") (pinfunction "3_3_A") (pintype "passive"))
      (node (ref "SOIL_TEMP") (pin "3_B") (pinfunction "3_3_B") (pintype "passive"))
      (node (ref "SOLAR") (pin "2") (pinfunction "2_2") (pintype "passive"))
      (node (ref "U1") (pin "2") (pinfunction "GND_2") (pintype "power_in"))
      (node (ref "U2") (pin "2") (pinfunction "GND_2") (pintype "power_in"))
      (node (ref "U3") (pin "2") (pinfunction "GND_2") (pintype "power_in"))
      (node (ref "U4") (pin "5") (pinfunction "GND_5") (pintype "power_in"))
      (node (ref "U5") (pin "2") (pinfunction "GND_2") (pintype "power_in"))
      (node (ref "U6") (pin "12") (pinfunction "GND_12") (pintype "power_in"))
      (node (ref "U6") (pin "3") (pinfunction "CP2_3") (pintype "input"))
      (node (ref "U6") (pin "6") (pinfunction "PR1_6") (pintype "input"))
      (node (ref "U6") (pin "9") (pinfunction "ST_9") (pintype "output"))
      (node (ref "U7") (pin "1") (pinfunction "PGND_1") (pintype "power_in"))
      (node (ref "U7") (pin "11") (pinfunction "PAD_11") (pintype "power_in"))
      (node (ref "U7") (pin "4") (pinfunction "NC_4") (pintype "passive"))
      (node (ref "U7") (pin "6") (pinfunction "AGND_6") (pintype "power_in"))
      (node (ref "U7") (pin "V") (pinfunction "TGND1_V") (pintype "bidirectional"))
      (node (ref "U7") (pin "V_1") (pinfunction "TGND2_V_1") (pintype "bidirectional"))
      (node (ref "U7") (pin "V_2") (pinfunction "TGND3_V_2") (pintype "bidirectional"))
      (node (ref "U8") (pin "2") (pinfunction "GND_2") (pintype "power_in"))
      (node (ref "U9") (pin "2") (pinfunction "GND_2") (pintype "power_in"))
    )
    (net (code "13") (name "GPIO11") (class "Default")
      (node (ref "S2MINI1") (pin "11") (pinfunction "IO11_11") (pintype "bidirectional"))
    )
    (net (code "14") (name "GPIO39") (class "Default")
      (node (ref "S2MINI1") (pin "39") (pinfunction "IO39_39") (pintype "bidirectional"))
    )
    (net (code "15") (name "GPIO40") (class "Default")
      (node (ref "S2MINI1") (pin "40") (pinfunction "IO40_40") (pintype "bidirectional"))
    )
    (net (code "16") (name "HEAT_PULSE") (class "Default")
      (node (ref "I2C") (pin "2_A") (pinfunction "2_2_A") (pintype "passive"))
      (node (ref "I2C") (pin "2_B") (pinfunction "2_2_B") (pintype "passive"))
      (node (ref "R54") (pin "2") (pinfunction "2_2") (pintype "passive"))
      (node (ref "S2MINI1") (pin "7") (pinfunction "IO7_7") (pintype "bidirectional"))
    )
    (net (code "17") (name "I2C_PORT_PWR_EN") (class "Default")
      (node (ref "Q4") (pin "5") (pinfunction "G1_5") (pintype "passive"))
      (node (ref "R9") (pin "2") (pinfunction "2_2") (pintype "passive"))
      (node (ref "S2MINI1") (pin "13") (pinfunction "IO13_13") (pintype "bidirectional"))
    )
    (net (code "18") (name "MISO") (class "Default")
      (node (ref "R20") (pin "1") (pinfunction "1_1") (pintype "passive"))
      (node (ref "RFM95W") (pin "2") (pinfunction "MISO_2") (pintype "input"))
      (node (ref "S2MINI1") (pin "37") (pinfunction "IO37_37") (pintype "bidirectional"))
      (node (ref "SD_CARD") (pin "7") (pinfunction "DAT0_7") (pintype "bidirectional"))
    )
    (net (code "19") (name "MOSI") (class "Default")
      (node (ref "R19") (pin "1") (pinfunction "1_1") (pintype "passive"))
      (node (ref "RFM95W") (pin "3") (pinfunction "MOSI_3") (pintype "output"))
      (node (ref "S2MINI1") (pin "35") (pinfunction "IO35_35") (pintype "bidirectional"))
      (node (ref "SD_CARD") (pin "3") (pinfunction "CMD_3") (pintype "bidirectional"))
    )
    (net (code "20") (name "Net-(CHRG-PadA)") (class "Default")
      (node (ref "CHRG") (pin "A") (pinfunction "A_A") (pintype "passive"))
      (node (ref "R36") (pin "1") (pinfunction "1_1") (pintype "passive"))
    )
    (net (code "21") (name "Net-(CN1-PadVBUS)") (class "Default")
      (node (ref "CN1") (pin "VBUS") (pinfunction "VBUS_VBUS") (pintype "power_in"))
      (node (ref "R32") (pin "1") (pinfunction "1_1") (pintype "passive"))
    )
    (net (code "22") (name "Net-(D1-PadA)") (class "Default")
      (node (ref "D1") (pin "A") (pinfunction "A_A") (pintype "passive"))
      (node (ref "SOLAR") (pin "1") (pinfunction "1_1") (pintype "passive"))
    )
    (net (code "23") (name "Net-(DONE-PadA)") (class "Default")
      (node (ref "DONE") (pin "A") (pinfunction "A_A") (pintype "passive"))
      (node (ref "R37") (pin "1") (pinfunction "1_1") (pintype "passive"))
    )
    (net (code "24") (name "Net-(IC1-FB)") (class "Default")
      (node (ref "C25") (pin "2") (pinfunction "2_2") (pintype "passive"))
      (node (ref "IC1") (pin "8") (pinfunction "FB_8") (pintype "input"))
      (node (ref "R34") (pin "1") (pinfunction "1_1") (pintype "passive"))
      (node (ref "R35") (pin "2") (pinfunction "2_2") (pintype "passive"))
    )
    (net (code "25") (name "Net-(IC1-L1)") (class "Default")
      (node (ref "IC1") (pin "1") (pinfunction "L1_1") (pintype "input"))
      (node (ref "L1") (pin "1") (pinfunction "1_1") (pintype "passive"))
    )
    (net (code "26") (name "Net-(IC1-L2)") (class "Default")
      (node (ref "IC1") (pin "10") (pinfunction "L2_10") (pintype "input"))
      (node (ref "L1") (pin "2") (pinfunction "2_2") (pintype "passive"))
    )
    (net (code "27") (name "Net-(IC1-PG)") (class "Default")
      (node (ref "IC1") (pin "5") (pinfunction "PG_5") (pintype "output"))
      (node (ref "R33") (pin "1") (pinfunction "1_1") (pintype "passive"))
    )
    (net (code "28") (name "Net-(IC1-VAUX)") (class "Default")
      (node (ref "C22") (pin "1") (pinfunction "1_1") (pintype "passive"))
      (node (ref "IC1") (pin "6") (pinfunction "VAUX_6") (pintype "power_in"))
    )
    (net (code "29") (name "Net-(IC2-PROG1)") (class "Default")
      (node (ref "IC2") (pin "P$13") (pinfunction "PROG1_P$13") (pintype "input"))
      (node (ref "R42") (pin "2") (pinfunction "2_2") (pintype "passive"))
    )
    (net (code "30") (name "Net-(IC2-PROG3)") (class "Default")
      (node (ref "IC2") (pin "P$12") (pinfunction "PROG3_P$12") (pintype "input"))
      (node (ref "R43") (pin "2") (pinfunction "2_2") (pintype "passive"))
    )
    (net (code "31") (name "Net-(IC2-SEL)") (class "Default")
      (node (ref "IC2") (pin "P$3") (pinfunction "SEL_P$3") (pintype "input"))
      (node (ref "R38") (pin "2") (pinfunction "2_2") (pintype "passive"))
    )
    (net (code "32") (name "Net-(IC2-STAT1{slash}LBO)") (class "Default")
      (node (ref "CHRG") (pin "C") (pinfunction "C_C") (pintype "passive"))
      (node (ref "IC2") (pin "P$8") (pinfunction "STAT1/LBO_P$8") (pintype "output"))
    )
    (net (code "33") (name "Net-(IC2-STAT2)") (class "Default")
      (node (ref "DONE") (pin "C") (pinfunction "C_C") (pintype "passive"))
      (node (ref "IC2") (pin "P$7") (pinfunction "STAT2_P$7") (pintype "output"))
    )
    (net (code "34") (name "Net-(IC2-THERM)") (class "Default")
      (node (ref "IC2") (pin "P$5") (pinfunction "THERM_P$5") (pintype "input"))
      (node (ref "R46") (pin "1") (pinfunction "1_1") (pintype "passive"))
    )
    (net (code "35") (name "Net-(IC2-VPCC)") (class "Default")
      (node (ref "IC2") (pin "P$2") (pinfunction "VPCC_P$2") (pintype "input"))
      (node (ref "R40") (pin "1") (pinfunction "1_1") (pintype "passive"))
      (node (ref "R41") (pin "1") (pinfunction "1_1") (pintype "passive"))
    )
    (net (code "36") (name "Net-(IC2-{slash}PG)") (class "Default")
      (node (ref "IC2") (pin "P$6") (pinfunction "/PG_P$6") (pintype "output"))
      (node (ref "PWR") (pin "C") (pinfunction "C_C") (pintype "passive"))
    )
    (net (code "37") (name "Net-(J7-SIG)") (class "Default")
      (node (ref "J7") (pin "1") (pinfunction "SIG_1") (pintype "passive"))
      (node (ref "RFM95W") (pin "9") (pinfunction "ANT_9") (pintype "bidirectional"))
    )
    (net (code "38") (name "Net-(PWR-PadA)") (class "Default")
      (node (ref "PWR") (pin "A") (pinfunction "A_A") (pintype "passive"))
      (node (ref "R39") (pin "1") (pinfunction "1_1") (pintype "passive"))
    )
    (net (code "39") (name "Net-(Q1-D)") (class "Default")
      (node (ref "Q1") (pin "3") (pinfunction "D_3") (pintype "passive"))
      (node (ref "Q2") (pin "3") (pinfunction "D_3") (pintype "passive"))
    )
    (net (code "40") (name "Net-(Q2-S)") (class "Default")
      (node (ref "Q2") (pin "2") (pinfunction "S_2") (pintype "passive"))
      (node (ref "R4") (pin "1") (pinfunction "1_1") (pintype "passive"))
      (node (ref "SDI-12") (pin "2_A") (pinfunction "2_2_A") (pintype "passive"))
      (node (ref "SDI-12") (pin "2_B") (pinfunction "2_2_B") (pintype "passive"))
    )
    (net (code "41") (name "Net-(Q3-D2_1)") (class "Default")
      (node (ref "C5") (pin "1") (pinfunction "1_1") (pintype "passive"))
      (node (ref "C6") (pin "2") (pinfunction "2_2") (pintype "passive"))
      (node (ref "Q3") (pin "2") (pinfunction "D2_1_2") (pintype "output"))
      (node (ref "Q3") (pin "3") (pinfunction "D2_2_3") (pintype "output"))
      (node (ref "SDI-12") (pin "1_A") (pinfunction "1_1_A") (pintype "passive"))
      (node (ref "SDI-12") (pin "1_B") (pinfunction "1_1_B") (pintype "passive"))
    )
    (net (code "42") (name "Net-(Q3-R1C1)") (class "Default")
      (node (ref "C6") (pin "1") (pinfunction "1_1") (pintype "passive"))
      (node (ref "Q3") (pin "6") (pinfunction "R1C1_6") (pintype "input"))
      (node (ref "R7") (pin "1") (pinfunction "1_1") (pintype "passive"))
    )
    (net (code "43") (name "Net-(Q3-R2)") (class "Default")
      (node (ref "Q3") (pin "1") (pinfunction "R2_1") (pintype "power_in"))
      (node (ref "R5") (pin "2") (pinfunction "2_2") (pintype "passive"))
    )
    (net (code "44") (name "Net-(Q4-D1{slash}G2)") (class "Default")
      (node (ref "C9") (pin "1") (pinfunction "1_1") (pintype "passive"))
      (node (ref "Q4") (pin "6") (pinfunction "D1/G2_6") (pintype "passive"))
      (node (ref "R8") (pin "1") (pinfunction "1_1") (pintype "passive"))
    )
    (net (code "45") (name "Net-(Q4-S1)") (class "Default")
      (node (ref "Q4") (pin "1") (pinfunction "S1_1") (pintype "passive"))
      (node (ref "R10") (pin "2") (pinfunction "2_2") (pintype "passive"))
    )
    (net (code "46") (name "Net-(Q5-D1{slash}G2)") (class "Default")
      (node (ref "C12") (pin "1") (pinfunction "1_1") (pintype "passive"))
      (node (ref "Q5") (pin "6") (pinfunction "D1/G2_6") (pintype "passive"))
      (node (ref "R15") (pin "1") (pinfunction "1_1") (pintype "passive"))
    )
    (net (code "47") (name "Net-(Q5-S1)") (class "Default")
      (node (ref "Q5") (pin "1") (pinfunction "S1_1") (pintype "passive"))
      (node (ref "R17") (pin "2") (pinfunction "2_2") (pintype "passive"))
    )
    (net (code "48") (name "Net-(Q6-D1{slash}G2)") (class "Default")
      (node (ref "C18") (pin "1") (pinfunction "1_1") (pintype "passive"))
      (node (ref "Q6") (pin "6") (pinfunction "D1/G2_6") (pintype "passive"))
      (node (ref "R26") (pin "1") (pinfunction "1_1") (pintype "passive"))
    )
    (net (code "49") (name "Net-(Q6-S1)") (class "Default")
      (node (ref "Q6") (pin "1") (pinfunction "S1_1") (pintype "passive"))
      (node (ref "R24") (pin "2") (pinfunction "2_2") (pintype "passive"))
    )
    (net (code "50") (name "Net-(R46-Pad2)") (class "Default")
      (node (ref "R46") (pin "2") (pinfunction "2_2") (pintype "passive"))
      (node (ref "R48") (pin "2") (pinfunction "2_2") (pintype "passive"))
      (node (ref "RT1") (pin "2") (pinfunction "2_2") (pintype "passive"))
    )
    (net (code "51") (name "Net-(R52-A)") (class "Default")
      (node (ref "R51") (pin "1") (pinfunction "1_1") (pintype "passive"))
      (node (ref "R52") (pin "1") (pinfunction "A_1") (pintype "passive"))
    )
    (net (code "52") (name "Net-(R52-E)") (class "Default")
      (node (ref "R52") (pin "3") (pinfunction "E_3") (pintype "passive"))
      (node (ref "R53") (pin "2") (pinfunction "2_2") (pintype "passive"))
    )
    (net (code "53") (name "Net-(R52-S)") (class "Default")
      (node (ref "R52") (pin "2") (pinfunction "S_2") (pintype "passive"))
      (node (ref "U9") (pin "3") (pinfunction "FB_3") (pintype "input"))
    )
    (net (code "54") (name "Net-(RFM95W-3.3V)") (class "Default")
      (node (ref "C17") (pin "1") (pinfunction "1_1") (pintype "passive"))
      (node (ref "C18") (pin "2") (pinfunction "2_2") (pintype "passive"))
      (node (ref "Q6") (pin "2") (pinfunction "D2_2") (pintype "passive"))
      (node (ref "Q6") (pin "3") (pinfunction "D2_3") (pintype "passive"))
      (node (ref "RFM95W") (pin "13") (pinfunction "3.3V_13") (pintype "power_in"))
    )
    (net (code "55") (name "Net-(SD_CARD-VDD)") (class "Default")
      (node (ref "C12") (pin "2") (pinfunction "2_2") (pintype "passive"))
      (node (ref "C13") (pin "1") (pinfunction "1_1") (pintype "passive"))
      (node (ref "C14") (pin "1") (pinfunction "1_1") (pintype "passive"))
      (node (ref "Q5") (pin "2") (pinfunction "D2_2") (pintype "passive"))
      (node (ref "Q5") (pin "3") (pinfunction "D2_3") (pintype "passive"))
      (node (ref "R18") (pin "2") (pinfunction "2_2") (pintype "passive"))
      (node (ref "R19") (pin "2") (pinfunction "2_2") (pintype "passive"))
      (node (ref "R20") (pin "2") (pinfunction "2_2") (pintype "passive"))
      (node (ref "R21") (pin "2") (pinfunction "2_2") (pintype "passive"))
      (node (ref "SD_CARD") (pin "4") (pinfunction "VDD_4") (pintype "power_in"))
    )
    (net (code "56") (name "Net-(U3-QOD)") (class "Default")
      (node (ref "C38") (pin "1") (pinfunction "1_1") (pintype "passive"))
      (node (ref "R12") (pin "2") (pinfunction "2_2") (pintype "passive"))
      (node (ref "R14") (pin "2") (pinfunction "2_2") (pintype "passive"))
      (node (ref "U3") (pin "5") (pinfunction "QOD_5") (pintype "output"))
      (node (ref "U3") (pin "6") (pinfunction "VOUT_6") (pintype "output"))
      (node (ref "U4") (pin "2") (pinfunction "VCC_2") (pintype "power_in"))
    )
    (net (code "57") (name "Net-(U4-VBAT)") (class "Default")
      (node (ref "BT1") (pin "P") (pinfunction "P_P") (pintype "passive"))
      (node (ref "U4") (pin "6") (pinfunction "VBAT_6") (pintype "power_in"))
    )
    (net (code "58") (name "Net-(U5-QOD)") (class "Default")
      (node (ref "R22") (pin "2") (pinfunction "2_2") (pintype "passive"))
      (node (ref "U5") (pin "5") (pinfunction "QOD_5") (pintype "output"))
      (node (ref "U5") (pin "6") (pinfunction "VOUT_6") (pintype "output"))
    )
    (net (code "59") (name "Net-(U6-ILIM)") (class "Default")
      (node (ref "R31") (pin "2") (pinfunction "2_2") (pintype "passive"))
      (node (ref "U6") (pin "10") (pinfunction "ILIM_10") (pintype "passive"))
    )
    (net (code "60") (name "Net-(U6-OV1)") (class "Default")
      (node (ref "R27") (pin "1") (pinfunction "1_1") (pintype "passive"))
      (node (ref "R28") (pin "2") (pinfunction "2_2") (pintype "passive"))
      (node (ref "U6") (pin "5") (pinfunction "OV1_5") (pintype "input"))
    )
    (net (code "61") (name "Net-(U6-OV2)") (class "Default")
      (node (ref "R29") (pin "1") (pinfunction "1_1") (pintype "passive"))
      (node (ref "R30") (pin "2") (pinfunction "2_2") (pintype "passive"))
      (node (ref "U6") (pin "4") (pinfunction "OV2_4") (pintype "input"))
    )
    (net (code "62") (name "Net-(U6-SS)") (class "Default")
      (node (ref "C23") (pin "1") (pinfunction "1_1") (pintype "passive"))
      (node (ref "U6") (pin "11") (pinfunction "SS_11") (pintype "passive"))
    )
    (net (code "63") (name "Net-(U7-EN)") (class "Default")
      (node (ref "C24") (pin "2") (pinfunction "2_2") (pintype "passive"))
      (node (ref "D1") (pin "C") (pinfunction "C_C") (pintype "passive"))
      (node (ref "U7") (pin "2") (pinfunction "VIN_2") (pintype "power_in"))
      (node (ref "U7") (pin "3") (pinfunction "EN_3") (pintype "input"))
    )
    (net (code "64") (name "Net-(U7-FB)") (class "Default")
      (node (ref "R44") (pin "2") (pinfunction "2_2") (pintype "passive"))
      (node (ref "R45") (pin "2") (pinfunction "2_2") (pintype "passive"))
      (node (ref "U7") (pin "5") (pinfunction "FB_5") (pintype "input"))
    )
    (net (code "65") (name "Net-(U7-PG)") (class "Default")
      (node (ref "R47") (pin "1") (pinfunction "1_1") (pintype "passive"))
      (node (ref "U7") (pin "7") (pinfunction "PG_7") (pintype "output"))
    )
    (net (code "66") (name "Net-(U7-SW)") (class "Default")
      (node (ref "L2") (pin "2") (pinfunction "2_2") (pintype "passive"))
      (node (ref "U7") (pin "9") (pinfunction "SW_9") (pintype "power_in"))
    )
    (net (code "67") (name "Net-(U8-FB)") (class "Default")
      (node (ref "R49") (pin "1") (pinfunction "1_1") (pintype "passive"))
      (node (ref "R50") (pin "2") (pinfunction "2_2") (pintype "passive"))
      (node (ref "U8") (pin "3") (pinfunction "FB_3") (pintype "input"))
    )
    (net (code "68") (name "Net-(U8-SW)") (class "Default")
      (node (ref "D2") (pin "A") (pinfunction "A_A") (pintype "passive"))
      (node (ref "L3") (pin "2") (pinfunction "2_2") (pintype "passive"))
      (node (ref "U8") (pin "1") (pinfunction "SW_1") (pintype "output"))
    )
    (net (code "69") (name "Net-(U9-SW)") (class "Default")
      (node (ref "D3") (pin "A") (pinfunction "A_A") (pintype "passive"))
      (node (ref "L4") (pin "2") (pinfunction "2_2") (pintype "passive"))
      (node (ref "U9") (pin "1") (pinfunction "SW_1") (pintype "output"))
    )
    (net (code "70") (name "RFM_CS") (class "Default")
      (node (ref "RFM95W") (pin "5") (pinfunction "NSS_5") (pintype "input"))
      (node (ref "S2MINI1") (pin "34") (pinfunction "IO34_34") (pintype "bidirectional"))
    )
    (net (code "71") (name "RFM_DIO0") (class "Default")
      (node (ref "RFM95W") (pin "14") (pinfunction "DIO0_14") (pintype "bidirectional"))
      (node (ref "S2MINI1") (pin "33") (pinfunction "IO33_33") (pintype "bidirectional"))
    )
    (net (code "72") (name "RFM_DIO1") (class "Default")
      (node (ref "RFM95W") (pin "15") (pinfunction "DIO1_15") (pintype "bidirectional"))
      (node (ref "S2MINI1") (pin "38") (pinfunction "IO38_38") (pintype "bidirectional"))
    )
    (net (code "73") (name "RFM_PWR_EN") (class "Default")
      (node (ref "Q6") (pin "5") (pinfunction "G1_5") (pintype "passive"))
      (node (ref "R25") (pin "2") (pinfunction "2_2") (pintype "passive"))
      (node (ref "S2MINI1") (pin "4") (pinfunction "IO4_4") (pintype "bidirectional"))
    )
    (net (code "74") (name "RFM_RESET") (class "Default")
      (node (ref "RFM95W") (pin "6") (pinfunction "RESET_6") (pintype "bidirectional"))
      (node (ref "S2MINI1") (pin "18") (pinfunction "IO18_18") (pintype "bidirectional"))
    )
    (net (code "75") (name "RTC_PWR_EN") (class "Default")
      (node (ref "S2MINI1") (pin "15") (pinfunction "IO15_15") (pintype "bidirectional"))
      (node (ref "U3") (pin "3") (pinfunction "ON_3") (pintype "input"))
    )
    (net (code "76") (name "SCK") (class "Default")
      (node (ref "R18") (pin "1") (pinfunction "1_1") (pintype "passive"))
      (node (ref "RFM95W") (pin "4") (pinfunction "SCK_4") (pintype "input"))
      (node (ref "S2MINI1") (pin "36") (pinfunction "IO36_36") (pintype "bidirectional"))
      (node (ref "SD_CARD") (pin "5") (pinfunction "CLK_5") (pintype "input"))
    )
    (net (code "77") (name "SCL") (class "Default")
      (node (ref "I2C") (pin "3_A") (pinfunction "3_3_A") (pintype "passive"))
      (node (ref "I2C") (pin "3_B") (pinfunction "3_3_B") (pintype "passive"))
      (node (ref "R11") (pin "1") (pinfunction "1_1") (pintype "passive"))
      (node (ref "R12") (pin "1") (pinfunction "1_1") (pintype "passive"))
      (node (ref "S2MINI1") (pin "21") (pinfunction "IO21_21") (pintype "bidirectional"))
      (node (ref "U4") (pin "8") (pinfunction "SCL_8") (pintype "input"))
    )
    (net (code "78") (name "SDA") (class "Default")
      (node (ref "I2C") (pin "4_A") (pinfunction "4_4_A") (pintype "passive"))
      (node (ref "I2C") (pin "4_B") (pinfunction "4_4_B") (pintype "passive"))
      (node (ref "R13") (pin "1") (pinfunction "1_1") (pintype "passive"))
      (node (ref "R14") (pin "1") (pinfunction "1_1") (pintype "passive"))
      (node (ref "S2MINI1") (pin "17") (pinfunction "IO17_17") (pintype "bidirectional"))
      (node (ref "U4") (pin "7") (pinfunction "SDA_7") (pintype "bidirectional"))
    )
    (net (code "79") (name "SDI12_DATA") (class "Default")
      (node (ref "Q1") (pin "2") (pinfunction "S_2") (pintype "passive"))
      (node (ref "R3") (pin "1") (pinfunction "1_1") (pintype "passive"))
      (node (ref "S2MINI1") (pin "14") (pinfunction "IO14_14") (pintype "bidirectional"))
    )
    (net (code "80") (name "SDI12_PWR_EN") (class "Default")
      (node (ref "Q3") (pin "5") (pinfunction "ON/OFF_5") (pintype "input"))
      (node (ref "R6") (pin "2") (pinfunction "2_2") (pintype "passive"))
      (node (ref "S2MINI1") (pin "9") (pinfunction "IO9_9") (pintype "bidirectional"))
      (node (ref "U2") (pin "3") (pinfunction "ON_3") (pintype "input"))
    )
    (net (code "81") (name "SD_CS") (class "Default")
      (node (ref "R21") (pin "1") (pinfunction "1_1") (pintype "passive"))
      (node (ref "S2MINI1") (pin "16") (pinfunction "IO16_16") (pintype "bidirectional"))
      (node (ref "SD_CARD") (pin "2") (pinfunction "CD/DAT3_2") (pintype "bidirectional"))
    )
    (net (code "82") (name "SD_PWR_EN") (class "Default")
      (node (ref "Q5") (pin "5") (pinfunction "G1_5") (pintype "passive"))
      (node (ref "R16") (pin "2") (pinfunction "2_2") (pintype "passive"))
      (node (ref "S2MINI1") (pin "10") (pinfunction "IO10_10") (pintype "bidirectional"))
    )
    (net (code "83") (name "SM_ADC") (class "Default")
      (node (ref "C3") (pin "1") (pinfunction "1_1") (pintype "passive"))
      (node (ref "S2MINI1") (pin "1") (pinfunction "IO1_1") (pintype "bidirectional"))
      (node (ref "SOIL_MOISTURE") (pin "2_A") (pinfunction "2_2_A") (pintype "passive"))
      (node (ref "SOIL_MOISTURE") (pin "2_B") (pinfunction "2_2_B") (pintype "passive"))
    )
    (net (code "84") (name "ST_DATA") (class "Default")
      (node (ref "R1") (pin "1") (pinfunction "1_1") (pintype "passive"))
      (node (ref "S2MINI1") (pin "2") (pinfunction "IO2_2") (pintype "bidirectional"))
      (node (ref "SOIL_TEMP") (pin "2_A") (pinfunction "2_2_A") (pintype "passive"))
      (node (ref "SOIL_TEMP") (pin "2_B") (pinfunction "2_2_B") (pintype "passive"))
    )
    (net (code "85") (name "VCC") (class "Default")
      (node (ref "C27") (pin "1") (pinfunction "1_1") (pintype "passive"))
      (node (ref "C29") (pin "1") (pinfunction "1_1") (pintype "passive"))
      (node (ref "IC2") (pin "P$17") (pinfunction "CE_P$17") (pintype "input"))
      (node (ref "IC2") (pin "P$18") (pinfunction "IN1_P$18") (pintype "input"))
      (node (ref "IC2") (pin "P$19") (pinfunction "IN2_P$19") (pintype "input"))
      (node (ref "IC2") (pin "P$4") (pinfunction "PROG2_P$4") (pintype "input"))
      (node (ref "IC2") (pin "P$9") (pinfunction "/TE_P$9") (pintype "input"))
      (node (ref "R36") (pin "2") (pinfunction "2_2") (pintype "passive"))
      (node (ref "R37") (pin "2") (pinfunction "2_2") (pintype "passive"))
      (node (ref "R39") (pin "2") (pinfunction "2_2") (pintype "passive"))
      (node (ref "R40") (pin "2") (pinfunction "2_2") (pintype "passive"))
      (node (ref "U6") (pin "1") (pinfunction "OUT_1") (pintype "output"))
      (node (ref "U6") (pin "1_1") (pinfunction "OUT_1_1") (pintype "output"))
      (node (ref "U6") (pin "8") (pinfunction "OUT_8") (pintype "output"))
      (node (ref "U6") (pin "8_1") (pinfunction "OUT_8_1") (pintype "output"))
    )
    (net (code "86") (name "VCC2") (class "Default")
      (node (ref "C32") (pin "1") (pinfunction "1_1") (pintype "passive"))
      (node (ref "IC2") (pin "P$1") (pinfunction "OUT1_P$1") (pintype "output"))
      (node (ref "IC2") (pin "P$20") (pinfunction "OUT2_P$20") (pintype "output"))
      (node (ref "S1") (pin "1") (pinfunction "1_1") (pintype "passive"))
    )
    (net (code "87") (name "VCC_SW") (class "Default")
      (node (ref "C20") (pin "1") (pinfunction "1_1") (pintype "passive"))
      (node (ref "C21") (pin "1") (pinfunction "1_1") (pintype "passive"))
      (node (ref "C34") (pin "1") (pinfunction "1_1") (pintype "passive"))
      (node (ref "C35") (pin "1") (pinfunction "1_1") (pintype "passive"))
      (node (ref "IC1") (pin "2") (pinfunction "VIN_2") (pintype "input"))
      (node (ref "IC1") (pin "3") (pinfunction "EN_3") (pintype "input"))
      (node (ref "L3") (pin "1") (pinfunction "1_1") (pintype "passive"))
      (node (ref "L4") (pin "1") (pinfunction "1_1") (pintype "passive"))
      (node (ref "S1") (pin "2") (pinfunction "2_2") (pintype "passive"))
      (node (ref "U8") (pin "4") (pinfunction "EN_4") (pintype "input"))
      (node (ref "U8") (pin "5") (pinfunction "IN_5") (pintype "input"))
      (node (ref "U9") (pin "4") (pinfunction "EN_4") (pintype "input"))
      (node (ref "U9") (pin "5") (pinfunction "IN_5") (pintype "input"))
    )
    (net (code "88") (name "VIN1") (class "Default")
      (node (ref "C31") (pin "2") (pinfunction "2_2") (pintype "passive"))
      (node (ref "L2") (pin "1") (pinfunction "1_1") (pintype "passive"))
      (node (ref "R27") (pin "2") (pinfunction "2_2") (pintype "passive"))
      (node (ref "R44") (pin "1") (pinfunction "1_1") (pintype "passive"))
      (node (ref "R47") (pin "2") (pinfunction "2_2") (pintype "passive"))
      (node (ref "U6") (pin "7") (pinfunction "IN1_7") (pintype "input"))
      (node (ref "U6") (pin "7_1") (pinfunction "IN1_7_1") (pintype "input"))
      (node (ref "U7") (pin "10") (pinfunction "VOS_10") (pintype "input"))
      (node (ref "U7") (pin "8") (pinfunction "SLEEP_8") (pintype "input"))
    )
    (net (code "89") (name "VIN2") (class "Default")
      (node (ref "R29") (pin "2") (pinfunction "2_2") (pintype "passive"))
      (node (ref "R32") (pin "2") (pinfunction "2_2") (pintype "passive"))
      (node (ref "U6") (pin "2") (pinfunction "IN2_2") (pintype "input"))
      (node (ref "U6") (pin "2_1") (pinfunction "IN2_2_1") (pintype "input"))
    )
    (net (code "90") (name "unconnected-(CN1-PadD+)") (class "Default")
      (node (ref "CN1") (pin "D+") (pinfunction "D+_D+") (pintype "bidirectional"))
    )
    (net (code "91") (name "unconnected-(CN1-PadD-)") (class "Default")
      (node (ref "CN1") (pin "D-") (pinfunction "D-_D-") (pintype "bidirectional"))
    )
    (net (code "92") (name "unconnected-(CN1-PadID)") (class "Default")
      (node (ref "CN1") (pin "ID") (pinfunction "ID_ID") (pintype "bidirectional"))
    )
    (net (code "93") (name "unconnected-(RFM95W-DIO2-Pad16)") (class "Default")
      (node (ref "RFM95W") (pin "16") (pinfunction "DIO2_16") (pintype "bidirectional"))
    )
    (net (code "94") (name "unconnected-(RFM95W-DIO3-Pad11)") (class "Default")
      (node (ref "RFM95W") (pin "11") (pinfunction "DIO3_11") (pintype "bidirectional"))
    )
    (net (code "95") (name "unconnected-(RFM95W-DIO4-Pad12)") (class "Default")
      (node (ref "RFM95W") (pin "12") (pinfunction "DIO4_12") (pintype "bidirectional"))
    )
    (net (code "96") (name "unconnected-(RFM95W-DIO5-Pad7)") (class "Default")
      (node (ref "RFM95W") (pin "7") (pinfunction "DIO5_7") (pintype "bidirectional"))
    )
    (net (code "97") (name "unconnected-(S2MINI1-IO12-Pad12)") (class "Default")
      (node (ref "S2MINI1") (pin "12") (pinfunction "IO12_12") (pintype "bidirectional"))
    )
    (net (code "98") (name "unconnected-(S2MINI1-PadEN)") (class "Default")
      (node (ref "S2MINI1") (pin "EN") (pinfunction "EN_EN") (pintype "bidirectional"))
    )
    (net (code "99") (name "unconnected-(S2MINI1-PadVBUS)") (class "Default")
      (node (ref "S2MINI1") (pin "VBUS") (pinfunction "VBUS_VBUS") (pintype "bidirectional"))
    )
    (net (code "100") (name "unconnected-(SD_CARD-DAT1-Pad8)") (class "Default")
      (node (ref "SD_CARD") (pin "8") (pinfunction "DAT1_8") (pintype "bidirectional"))
    )
    (net (code "101") (name "unconnected-(SD_CARD-DAT2-Pad1)") (class "Default")
      (node (ref "SD_CARD") (pin "1") (pinfunction "DAT2_1") (pintype "bidirectional"))
    )
    (net (code "102") (name "unconnected-(SD_CARD-PadCD)") (class "Default")
      (node (ref "SD_CARD") (pin "CD") (pinfunction "CD_CD") (pintype "passive"))
    )
    (net (code "103") (name "unconnected-(U1-CT-Pad4)") (class "Default")
      (node (ref "U1") (pin "4") (pinfunction "CT_4") (pintype "output"))
    )
    (net (code "104") (name "unconnected-(U2-CT-Pad4)") (class "Default")
      (node (ref "U2") (pin "4") (pinfunction "CT_4") (pintype "output"))
    )
    (net (code "105") (name "unconnected-(U3-CT-Pad4)") (class "Default")
      (node (ref "U3") (pin "4") (pinfunction "CT_4") (pintype "output"))
    )
    (net (code "106") (name "unconnected-(U4-32KHZ-Pad1)") (class "Default")
      (node (ref "U4") (pin "1") (pinfunction "32KHZ_1") (pintype "output"))
    )
    (net (code "107") (name "unconnected-(U4-~{INT{slash}SQW}-Pad3)") (class "Default")
      (node (ref "U4") (pin "3") (pinfunction "~{INT/SQW}_3") (pintype "output"))
    )
    (net (code "108") (name "unconnected-(U4-~{RST}-Pad4)") (class "Default")
      (node (ref "U4") (pin "4") (pinfunction "~{RST}_4") (pintype "bidirectional"))
    )
    (net (code "109") (name "unconnected-(U5-CT-Pad4)") (class "Default")
      (node (ref "U5") (pin "4") (pinfunction "CT_4") (pintype "output"))
    )
  )
)
